# Clock_Distribution_PLL.net
KiCad netlist of a schematic drawn in Altium Designer
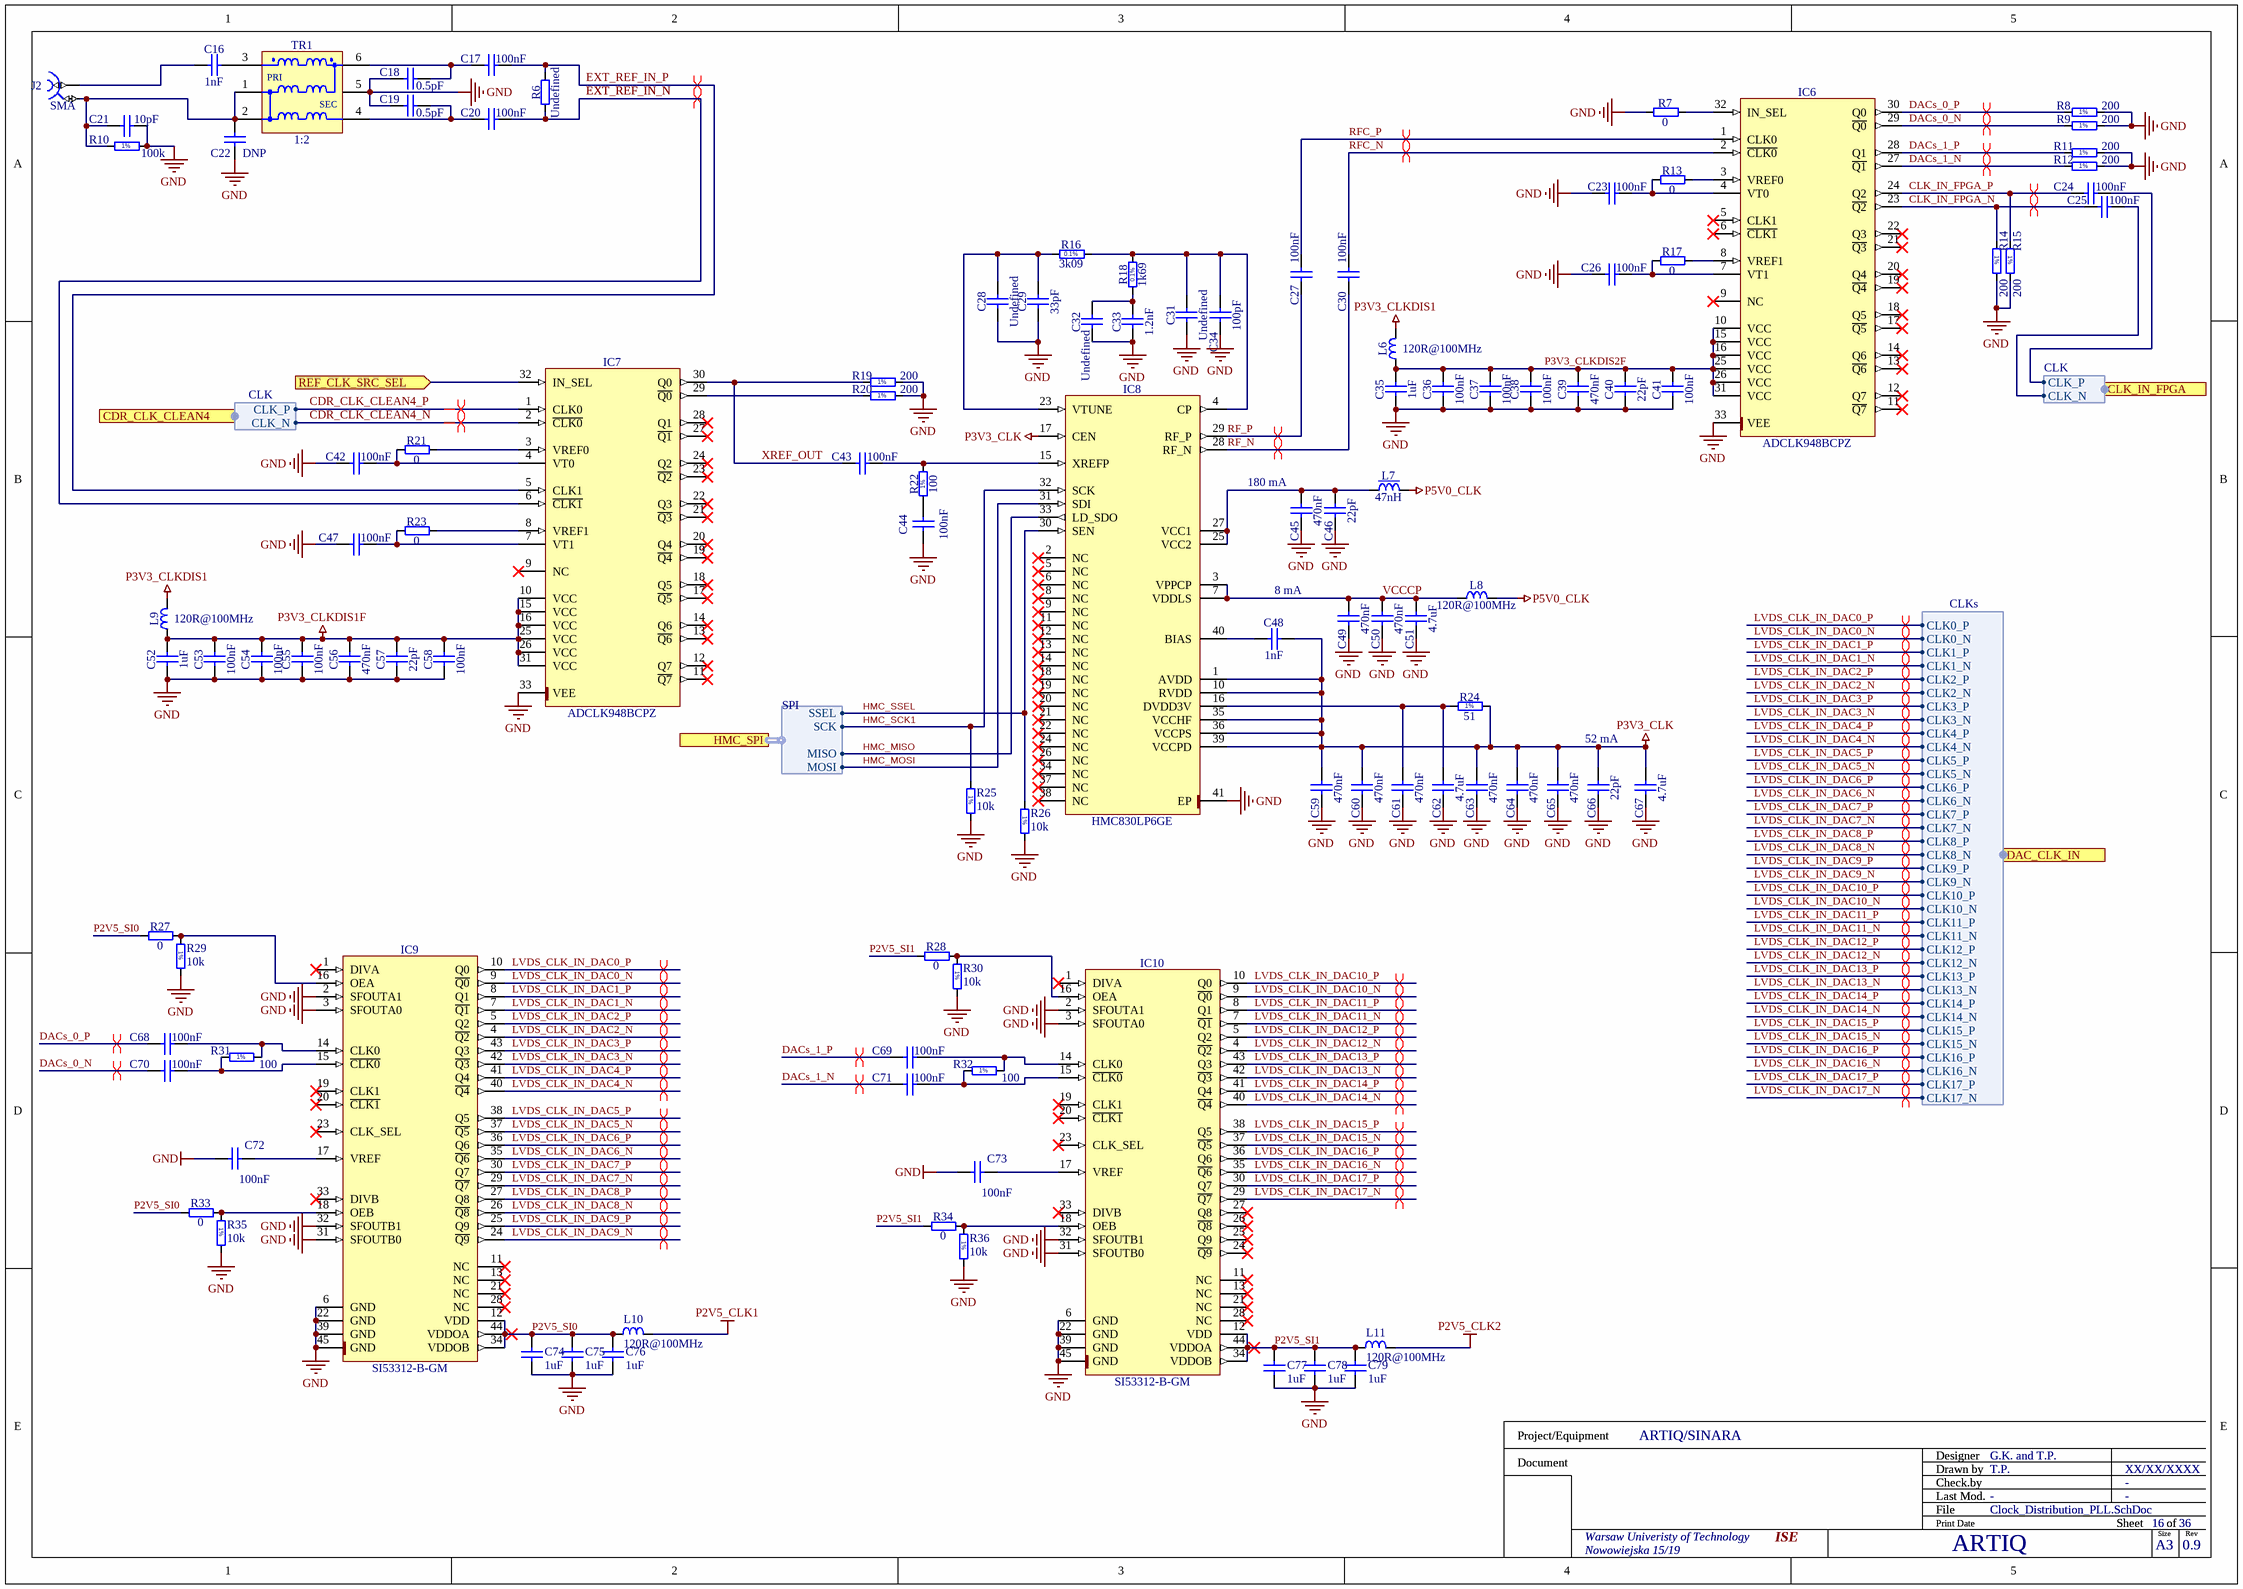
[diagram p0: Clock_Distribution_PLL.SchDoc]

(export (version "E")
  (design (tool "Eeschema 10.0.6"))
  (components
    (comp (ref "C16")
      (value "1nF")
      (footprint "CAPC1005X55N")
      (description "Non-polarised capacitor")
      (fields
        (field (name "PART NUMBER") "CC0402_1NF_50V_10%_X7R")
        (field (name "VOLTAGE") "50V")
        (field (name "AUTHOR") "CERN DEM JLC")
      )
      (libsource (lib "Capacitors") (part "Capacitor - non polarized"))
    )
    (comp (ref "C17")
      (value "100nF")
      (footprint "CAPC0603X33N")
      (description "Non-polarised capacitor")
      (fields
        (field (name "PART NUMBER") "CC0201_100NF_6.3V_10%_X5R")
        (field (name "VOLTAGE") "6.3V")
        (field (name "AUTHOR") "CERN DEM JLC")
      )
      (libsource (lib "Capacitors") (part "Capacitor - non polarized"))
    )
    (comp (ref "C18")
      (value "0.5pF")
      (footprint "CAPC1005X50N")
      (description "Non-polarised capacitor")
      (fields
        (field (name "PART NUMBER") "CC0402_0.5PF_25V_0.05PF_AVX_04023J0R5ABSTR")
        (field (name "VOLTAGE") "25V")
        (field (name "AUTHOR") "CERN DEM JLC")
      )
      (libsource (lib "Capacitors") (part "Capacitor - non polarized"))
    )
    (comp (ref "C19")
      (value "0.5pF")
      (footprint "CAPC1005X50N")
      (description "Non-polarised capacitor")
      (fields
        (field (name "PART NUMBER") "CC0402_0.5PF_25V_0.05PF_AVX_04023J0R5ABSTR")
        (field (name "VOLTAGE") "25V")
        (field (name "AUTHOR") "CERN DEM JLC")
      )
      (libsource (lib "Capacitors") (part "Capacitor - non polarized"))
    )
    (comp (ref "C20")
      (value "100nF")
      (footprint "CAPC0603X33N")
      (description "Non-polarised capacitor")
      (fields
        (field (name "PART NUMBER") "CC0201_100NF_6.3V_10%_X5R")
        (field (name "VOLTAGE") "6.3V")
        (field (name "AUTHOR") "CERN DEM JLC")
      )
      (libsource (lib "Capacitors") (part "Capacitor - non polarized"))
    )
    (comp (ref "C21")
      (value "10pF")
      (footprint "CAPC1608X87N")
      (description "Non-polarised capacitor")
      (fields
        (field (name "PART NUMBER") "CC0603_10PF_50V_5%_NP0")
        (field (name "VOLTAGE") "50V")
        (field (name "AUTHOR") "CERN DEM JLC")
      )
      (libsource (lib "Capacitors") (part "Capacitor - non polarized"))
    )
    (comp (ref "C22")
      (value "DNP")
      (footprint "CAPC0603X33N")
      (description "Non-polarised capacitor")
      (fields
        (field (name "PART NUMBER") "CC0201_100NF_6.3V_10%_X5R")
        (field (name "VOLTAGE") "6.3V")
        (field (name "AUTHOR") "CERN DEM JLC")
      )
      (libsource (lib "Capacitors") (part "Capacitor - non polarized"))
    )
    (comp (ref "C23")
      (value "100nF")
      (footprint "CAPC0603X33N")
      (description "Non-polarised capacitor")
      (fields
        (field (name "PART NUMBER") "CC0201_100NF_6.3V_10%_X5R")
        (field (name "VOLTAGE") "6.3V")
        (field (name "AUTHOR") "CERN DEM JLC")
      )
      (libsource (lib "Capacitors") (part "Capacitor - non polarized"))
    )
    (comp (ref "C24")
      (value "100nF")
      (footprint "CAPC0603X33N")
      (description "Non-polarised capacitor")
      (fields
        (field (name "PART NUMBER") "CC0201_100NF_6.3V_10%_X5R")
        (field (name "VOLTAGE") "6.3V")
        (field (name "AUTHOR") "CERN DEM JLC")
      )
      (libsource (lib "Capacitors") (part "Capacitor - non polarized"))
    )
    (comp (ref "C25")
      (value "100nF")
      (footprint "CAPC0603X33N")
      (description "Non-polarised capacitor")
      (fields
        (field (name "PART NUMBER") "CC0201_100NF_6.3V_10%_X5R")
        (field (name "VOLTAGE") "6.3V")
        (field (name "AUTHOR") "CERN DEM JLC")
      )
      (libsource (lib "Capacitors") (part "Capacitor - non polarized"))
    )
    (comp (ref "C26")
      (value "100nF")
      (footprint "CAPC0603X33N")
      (description "Non-polarised capacitor")
      (fields
        (field (name "PART NUMBER") "CC0201_100NF_6.3V_10%_X5R")
        (field (name "VOLTAGE") "6.3V")
        (field (name "AUTHOR") "CERN DEM JLC")
      )
      (libsource (lib "Capacitors") (part "Capacitor - non polarized"))
    )
    (comp (ref "C27")
      (value "100nF")
      (footprint "CAPC0603X33N")
      (description "Non-polarised capacitor")
      (fields
        (field (name "PART NUMBER") "CC0201_100NF_6.3V_10%_X5R")
        (field (name "VOLTAGE") "6.3V")
        (field (name "AUTHOR") "CERN DEM JLC")
      )
      (libsource (lib "Capacitors") (part "Capacitor - non polarized"))
    )
    (comp (ref "C28")
      (value "Undefined")
      (footprint "CAPC2012X135N")
      (description "Non-polarised capacitor")
      (fields
        (field (name "PART NUMBER") "Capacitor - non polarized CAPC2012X135N")
        (field (name "MANUFACTURER PART NUMBER") "CC0805_NO-VALUE")
        (field (name "AUTHOR") "CERN DEM JLC")
      )
      (libsource (lib "Capacitors") (part "Capacitor - non polarized"))
    )
    (comp (ref "C29")
      (value "33pF")
      (footprint "CAPC1608X87N")
      (description "Non-polarised capacitor")
      (fields
        (field (name "PART NUMBER") "CC0603_33PF_50V_5%_NP0")
        (field (name "VOLTAGE") "50V")
        (field (name "AUTHOR") "CERN DEM JLC")
      )
      (libsource (lib "Capacitors") (part "Capacitor - non polarized"))
    )
    (comp (ref "C30")
      (value "100nF")
      (footprint "CAPC0603X33N")
      (description "Non-polarised capacitor")
      (fields
        (field (name "PART NUMBER") "CC0201_100NF_6.3V_10%_X5R")
        (field (name "VOLTAGE") "6.3V")
        (field (name "AUTHOR") "CERN DEM JLC")
      )
      (libsource (lib "Capacitors") (part "Capacitor - non polarized"))
    )
    (comp (ref "C31")
      (value "Undefined")
      (footprint "CAPC2012X135N")
      (description "Non-polarised capacitor")
      (fields
        (field (name "PART NUMBER") "Capacitor - non polarized CAPC2012X135N")
        (field (name "MANUFACTURER PART NUMBER") "CC0805_NO-VALUE")
        (field (name "AUTHOR") "CERN DEM JLC")
      )
      (libsource (lib "Capacitors") (part "Capacitor - non polarized"))
    )
    (comp (ref "C32")
      (value "Undefined")
      (footprint "CAPC2012X135N")
      (description "Non-polarised capacitor")
      (fields
        (field (name "PART NUMBER") "Capacitor - non polarized CAPC2012X135N")
        (field (name "MANUFACTURER PART NUMBER") "CC0805_NO-VALUE")
        (field (name "AUTHOR") "CERN DEM JLC")
      )
      (libsource (lib "Capacitors") (part "Capacitor - non polarized"))
    )
    (comp (ref "C33")
      (value "1.2nF")
      (footprint "CAPC3216X140N")
      (description "Non-polarised capacitor")
      (fields
        (field (name "PART NUMBER") "CC1206_1.2NF_50V_5%_NP0")
        (field (name "VOLTAGE") "50V")
        (field (name "AUTHOR") "CERN DEM JLC")
      )
      (libsource (lib "Capacitors") (part "Capacitor - non polarized"))
    )
    (comp (ref "C34")
      (value "100pF")
      (footprint "CAPC1608X87N")
      (description "Non-polarised capacitor")
      (fields
        (field (name "PART NUMBER") "CC0603_100PF_50V_5%_NP0")
        (field (name "VOLTAGE") "50V")
        (field (name "AUTHOR") "CERN DEM JLC")
      )
      (libsource (lib "Capacitors") (part "Capacitor - non polarized"))
    )
    (comp (ref "C35")
      (value "1uF")
      (footprint "CAPC1005X55N")
      (description "Non-polarised capacitor")
      (fields
        (field (name "PART NUMBER") "CC0402_1UF_16V_10%_X5R")
        (field (name "VOLTAGE") "16V")
        (field (name "AUTHOR") "CERN DEM JLC")
      )
      (libsource (lib "Capacitors") (part "Capacitor - non polarized"))
    )
    (comp (ref "C36")
      (value "100nF")
      (footprint "CAPC0603X33N")
      (description "Non-polarised capacitor")
      (fields
        (field (name "PART NUMBER") "CC0201_100NF_6.3V_10%_X5R")
        (field (name "VOLTAGE") "6.3V")
        (field (name "AUTHOR") "CERN DEM JLC")
      )
      (libsource (lib "Capacitors") (part "Capacitor - non polarized"))
    )
    (comp (ref "C37")
      (value "100nF")
      (footprint "CAPC0603X33N")
      (description "Non-polarised capacitor")
      (fields
        (field (name "PART NUMBER") "CC0201_100NF_6.3V_10%_X5R")
        (field (name "VOLTAGE") "6.3V")
        (field (name "AUTHOR") "CERN DEM JLC")
      )
      (libsource (lib "Capacitors") (part "Capacitor - non polarized"))
    )
    (comp (ref "C38")
      (value "100nF")
      (footprint "CAPC0603X33N")
      (description "Non-polarised capacitor")
      (fields
        (field (name "PART NUMBER") "CC0201_100NF_6.3V_10%_X5R")
        (field (name "VOLTAGE") "6.3V")
        (field (name "AUTHOR") "CERN DEM JLC")
      )
      (libsource (lib "Capacitors") (part "Capacitor - non polarized"))
    )
    (comp (ref "C39")
      (value "470nF")
      (footprint "CAPC1005X55N")
      (description "Non-polarised capacitor")
      (fields
        (field (name "PART NUMBER") "CC0402_470NF_16V_10%_X5R")
        (field (name "VOLTAGE") "16V")
        (field (name "AUTHOR") "CERN DEM JLC")
      )
      (libsource (lib "Capacitors") (part "Capacitor - non polarized"))
    )
    (comp (ref "C40")
      (value "22pF")
      (footprint "CAPC1005X55N")
      (description "Non-polarised capacitor")
      (fields
        (field (name "PART NUMBER") "CC0402_22PF_50V_5%_C0G")
        (field (name "VOLTAGE") "50V")
        (field (name "AUTHOR") "CERN DEM JLC")
      )
      (libsource (lib "Capacitors") (part "Capacitor - non polarized"))
    )
    (comp (ref "C41")
      (value "100nF")
      (footprint "CAPC0603X33N")
      (description "Non-polarised capacitor")
      (fields
        (field (name "PART NUMBER") "CC0201_100NF_6.3V_10%_X5R")
        (field (name "VOLTAGE") "6.3V")
        (field (name "AUTHOR") "CERN DEM JLC")
      )
      (libsource (lib "Capacitors") (part "Capacitor - non polarized"))
    )
    (comp (ref "C42")
      (value "100nF")
      (footprint "CAPC0603X33N")
      (description "Non-polarised capacitor")
      (fields
        (field (name "PART NUMBER") "CC0201_100NF_6.3V_10%_X5R")
        (field (name "VOLTAGE") "6.3V")
        (field (name "AUTHOR") "CERN DEM JLC")
      )
      (libsource (lib "Capacitors") (part "Capacitor - non polarized"))
    )
    (comp (ref "C43")
      (value "100nF")
      (footprint "CAPC0603X33N")
      (description "Non-polarised capacitor")
      (fields
        (field (name "PART NUMBER") "CC0201_100NF_6.3V_10%_X5R")
        (field (name "VOLTAGE") "6.3V")
        (field (name "AUTHOR") "CERN DEM JLC")
      )
      (libsource (lib "Capacitors") (part "Capacitor - non polarized"))
    )
    (comp (ref "C44")
      (value "100nF")
      (footprint "CAPC0603X33N")
      (description "Non-polarised capacitor")
      (fields
        (field (name "PART NUMBER") "CC0201_100NF_6.3V_10%_X5R")
        (field (name "VOLTAGE") "6.3V")
        (field (name "AUTHOR") "CERN DEM JLC")
      )
      (libsource (lib "Capacitors") (part "Capacitor - non polarized"))
    )
    (comp (ref "C45")
      (value "470nF")
      (footprint "CAPC1005X55N")
      (description "Non-polarised capacitor")
      (fields
        (field (name "PART NUMBER") "CC0402_470NF_16V_10%_X5R")
        (field (name "VOLTAGE") "16V")
        (field (name "AUTHOR") "CERN DEM JLC")
      )
      (libsource (lib "Capacitors") (part "Capacitor - non polarized"))
    )
    (comp (ref "C46")
      (value "22pF")
      (footprint "CAPC1005X55N")
      (description "Non-polarised capacitor")
      (fields
        (field (name "PART NUMBER") "CC0402_22PF_50V_5%_C0G")
        (field (name "VOLTAGE") "50V")
        (field (name "AUTHOR") "CERN DEM JLC")
      )
      (libsource (lib "Capacitors") (part "Capacitor - non polarized"))
    )
    (comp (ref "C47")
      (value "100nF")
      (footprint "CAPC0603X33N")
      (description "Non-polarised capacitor")
      (fields
        (field (name "PART NUMBER") "CC0201_100NF_6.3V_10%_X5R")
        (field (name "VOLTAGE") "6.3V")
        (field (name "AUTHOR") "CERN DEM JLC")
      )
      (libsource (lib "Capacitors") (part "Capacitor - non polarized"))
    )
    (comp (ref "C48")
      (value "1nF")
      (footprint "CAPC1005X55N")
      (description "Non-polarised capacitor")
      (fields
        (field (name "PART NUMBER") "CC0402_1NF_50V_10%_X7R")
        (field (name "VOLTAGE") "50V")
        (field (name "AUTHOR") "CERN DEM JLC")
      )
      (libsource (lib "Capacitors") (part "Capacitor - non polarized"))
    )
    (comp (ref "C49")
      (value "470nF")
      (footprint "CAPC1005X55N")
      (description "Non-polarised capacitor")
      (fields
        (field (name "PART NUMBER") "CC0402_470NF_16V_10%_X5R")
        (field (name "VOLTAGE") "16V")
        (field (name "AUTHOR") "CERN DEM JLC")
      )
      (libsource (lib "Capacitors") (part "Capacitor - non polarized"))
    )
    (comp (ref "C50")
      (value "470nF")
      (footprint "CAPC1005X55N")
      (description "Non-polarised capacitor")
      (fields
        (field (name "PART NUMBER") "CC0402_470NF_16V_10%_X5R")
        (field (name "VOLTAGE") "16V")
        (field (name "AUTHOR") "CERN DEM JLC")
      )
      (libsource (lib "Capacitors") (part "Capacitor - non polarized"))
    )
    (comp (ref "C51")
      (value "4.7uF")
      (footprint "CAPC1608X90N")
      (description "Non-polarised capacitor")
      (fields
        (field (name "PART NUMBER") "CC0603_4.7UF_25V_10%_X5R")
        (field (name "VOLTAGE") "25V")
        (field (name "AUTHOR") "CERN DEM JLC")
      )
      (libsource (lib "Capacitors") (part "Capacitor - non polarized"))
    )
    (comp (ref "C52")
      (value "1uF")
      (footprint "CAPC1005X55N")
      (description "Non-polarised capacitor")
      (fields
        (field (name "PART NUMBER") "CC0402_1UF_16V_10%_X5R")
        (field (name "VOLTAGE") "16V")
        (field (name "AUTHOR") "CERN DEM JLC")
      )
      (libsource (lib "Capacitors") (part "Capacitor - non polarized"))
    )
    (comp (ref "C53")
      (value "100nF")
      (footprint "CAPC0603X33N")
      (description "Non-polarised capacitor")
      (fields
        (field (name "PART NUMBER") "CC0201_100NF_6.3V_10%_X5R")
        (field (name "VOLTAGE") "6.3V")
        (field (name "AUTHOR") "CERN DEM JLC")
      )
      (libsource (lib "Capacitors") (part "Capacitor - non polarized"))
    )
    (comp (ref "C54")
      (value "100nF")
      (footprint "CAPC0603X33N")
      (description "Non-polarised capacitor")
      (fields
        (field (name "PART NUMBER") "CC0201_100NF_6.3V_10%_X5R")
        (field (name "VOLTAGE") "6.3V")
        (field (name "AUTHOR") "CERN DEM JLC")
      )
      (libsource (lib "Capacitors") (part "Capacitor - non polarized"))
    )
    (comp (ref "C55")
      (value "100nF")
      (footprint "CAPC0603X33N")
      (description "Non-polarised capacitor")
      (fields
        (field (name "PART NUMBER") "CC0201_100NF_6.3V_10%_X5R")
        (field (name "VOLTAGE") "6.3V")
        (field (name "AUTHOR") "CERN DEM JLC")
      )
      (libsource (lib "Capacitors") (part "Capacitor - non polarized"))
    )
    (comp (ref "C56")
      (value "470nF")
      (footprint "CAPC1005X55N")
      (description "Non-polarised capacitor")
      (fields
        (field (name "PART NUMBER") "CC0402_470NF_16V_10%_X5R")
        (field (name "VOLTAGE") "16V")
        (field (name "AUTHOR") "CERN DEM JLC")
      )
      (libsource (lib "Capacitors") (part "Capacitor - non polarized"))
    )
    (comp (ref "C57")
      (value "22pF")
      (footprint "CAPC1005X55N")
      (description "Non-polarised capacitor")
      (fields
        (field (name "PART NUMBER") "CC0402_22PF_50V_5%_C0G")
        (field (name "VOLTAGE") "50V")
        (field (name "AUTHOR") "CERN DEM JLC")
      )
      (libsource (lib "Capacitors") (part "Capacitor - non polarized"))
    )
    (comp (ref "C58")
      (value "100nF")
      (footprint "CAPC0603X33N")
      (description "Non-polarised capacitor")
      (fields
        (field (name "PART NUMBER") "CC0201_100NF_6.3V_10%_X5R")
        (field (name "VOLTAGE") "6.3V")
        (field (name "AUTHOR") "CERN DEM JLC")
      )
      (libsource (lib "Capacitors") (part "Capacitor - non polarized"))
    )
    (comp (ref "C59")
      (value "470nF")
      (footprint "CAPC1005X55N")
      (description "Non-polarised capacitor")
      (fields
        (field (name "PART NUMBER") "CC0402_470NF_16V_10%_X5R")
        (field (name "VOLTAGE") "16V")
        (field (name "AUTHOR") "CERN DEM JLC")
      )
      (libsource (lib "Capacitors") (part "Capacitor - non polarized"))
    )
    (comp (ref "C60")
      (value "470nF")
      (footprint "CAPC1005X55N")
      (description "Non-polarised capacitor")
      (fields
        (field (name "PART NUMBER") "CC0402_470NF_16V_10%_X5R")
        (field (name "VOLTAGE") "16V")
        (field (name "AUTHOR") "CERN DEM JLC")
      )
      (libsource (lib "Capacitors") (part "Capacitor - non polarized"))
    )
    (comp (ref "C61")
      (value "470nF")
      (footprint "CAPC1005X55N")
      (description "Non-polarised capacitor")
      (fields
        (field (name "PART NUMBER") "CC0402_470NF_16V_10%_X5R")
        (field (name "VOLTAGE") "16V")
        (field (name "AUTHOR") "CERN DEM JLC")
      )
      (libsource (lib "Capacitors") (part "Capacitor - non polarized"))
    )
    (comp (ref "C62")
      (value "4.7uF")
      (footprint "CAPC1608X90N")
      (description "Non-polarised capacitor")
      (fields
        (field (name "PART NUMBER") "CC0603_4.7UF_25V_10%_X5R")
        (field (name "VOLTAGE") "25V")
        (field (name "AUTHOR") "CERN DEM JLC")
      )
      (libsource (lib "Capacitors") (part "Capacitor - non polarized"))
    )
    (comp (ref "C63")
      (value "470nF")
      (footprint "CAPC1005X55N")
      (description "Non-polarised capacitor")
      (fields
        (field (name "PART NUMBER") "CC0402_470NF_16V_10%_X5R")
        (field (name "VOLTAGE") "16V")
        (field (name "AUTHOR") "CERN DEM JLC")
      )
      (libsource (lib "Capacitors") (part "Capacitor - non polarized"))
    )
    (comp (ref "C64")
      (value "470nF")
      (footprint "CAPC1005X55N")
      (description "Non-polarised capacitor")
      (fields
        (field (name "PART NUMBER") "CC0402_470NF_16V_10%_X5R")
        (field (name "VOLTAGE") "16V")
        (field (name "AUTHOR") "CERN DEM JLC")
      )
      (libsource (lib "Capacitors") (part "Capacitor - non polarized"))
    )
    (comp (ref "C65")
      (value "470nF")
      (footprint "CAPC1005X55N")
      (description "Non-polarised capacitor")
      (fields
        (field (name "PART NUMBER") "CC0402_470NF_16V_10%_X5R")
        (field (name "VOLTAGE") "16V")
        (field (name "AUTHOR") "CERN DEM JLC")
      )
      (libsource (lib "Capacitors") (part "Capacitor - non polarized"))
    )
    (comp (ref "C66")
      (value "22pF")
      (footprint "CAPC1005X55N")
      (description "Non-polarised capacitor")
      (fields
        (field (name "PART NUMBER") "CC0402_22PF_50V_5%_C0G")
        (field (name "VOLTAGE") "50V")
        (field (name "AUTHOR") "CERN DEM JLC")
      )
      (libsource (lib "Capacitors") (part "Capacitor - non polarized"))
    )
    (comp (ref "C67")
      (value "4.7uF")
      (footprint "CAPC1608X90N")
      (description "Non-polarised capacitor")
      (fields
        (field (name "PART NUMBER") "CC0603_4.7UF_25V_10%_X5R")
        (field (name "VOLTAGE") "25V")
        (field (name "AUTHOR") "CERN DEM JLC")
      )
      (libsource (lib "Capacitors") (part "Capacitor - non polarized"))
    )
    (comp (ref "C68")
      (value "100nF")
      (footprint "CAPC0603X33N")
      (description "Non-polarised capacitor")
      (fields
        (field (name "PART NUMBER") "CC0201_100NF_6.3V_10%_X5R")
        (field (name "VOLTAGE") "6.3V")
        (field (name "AUTHOR") "CERN DEM JLC")
      )
      (libsource (lib "Capacitors") (part "Capacitor - non polarized"))
    )
    (comp (ref "C69")
      (value "100nF")
      (footprint "CAPC0603X33N")
      (description "Non-polarised capacitor")
      (fields
        (field (name "PART NUMBER") "CC0201_100NF_6.3V_10%_X5R")
        (field (name "VOLTAGE") "6.3V")
        (field (name "AUTHOR") "CERN DEM JLC")
      )
      (libsource (lib "Capacitors") (part "Capacitor - non polarized"))
    )
    (comp (ref "C70")
      (value "100nF")
      (footprint "CAPC0603X33N")
      (description "Non-polarised capacitor")
      (fields
        (field (name "PART NUMBER") "CC0201_100NF_6.3V_10%_X5R")
        (field (name "VOLTAGE") "6.3V")
        (field (name "AUTHOR") "CERN DEM JLC")
      )
      (libsource (lib "Capacitors") (part "Capacitor - non polarized"))
    )
    (comp (ref "C71")
      (value "100nF")
      (footprint "CAPC0603X33N")
      (description "Non-polarised capacitor")
      (fields
        (field (name "PART NUMBER") "CC0201_100NF_6.3V_10%_X5R")
        (field (name "VOLTAGE") "6.3V")
        (field (name "AUTHOR") "CERN DEM JLC")
      )
      (libsource (lib "Capacitors") (part "Capacitor - non polarized"))
    )
    (comp (ref "C72")
      (value "100nF")
      (footprint "CAPC1005X55N")
      (description "Non-polarised capacitor")
      (fields
        (field (name "PART NUMBER") "CC0402_100NF_16V_10%_X5R")
        (field (name "VOLTAGE") "16V")
        (field (name "AUTHOR") "CERN DEM JLC")
      )
      (libsource (lib "Capacitors") (part "Capacitor - non polarized"))
    )
    (comp (ref "C73")
      (value "100nF")
      (footprint "CAPC1005X55N")
      (description "Non-polarised capacitor")
      (fields
        (field (name "PART NUMBER") "CC0402_100NF_16V_10%_X5R")
        (field (name "VOLTAGE") "16V")
        (field (name "AUTHOR") "CERN DEM JLC")
      )
      (libsource (lib "Capacitors") (part "Capacitor - non polarized"))
    )
    (comp (ref "C74")
      (value "1uF")
      (footprint "CAPC1005X55N")
      (description "Non-polarised capacitor")
      (fields
        (field (name "PART NUMBER") "CC0402_1UF_16V_10%_X5R")
        (field (name "VOLTAGE") "16V")
        (field (name "AUTHOR") "CERN DEM JLC")
      )
      (libsource (lib "Capacitors") (part "Capacitor - non polarized"))
    )
    (comp (ref "C75")
      (value "1uF")
      (footprint "CAPC1005X55N")
      (description "Non-polarised capacitor")
      (fields
        (field (name "PART NUMBER") "CC0402_1UF_16V_10%_X5R")
        (field (name "VOLTAGE") "16V")
        (field (name "AUTHOR") "CERN DEM JLC")
      )
      (libsource (lib "Capacitors") (part "Capacitor - non polarized"))
    )
    (comp (ref "C76")
      (value "1uF")
      (footprint "CAPC1005X55N")
      (description "Non-polarised capacitor")
      (fields
        (field (name "PART NUMBER") "CC0402_1UF_16V_10%_X5R")
        (field (name "VOLTAGE") "16V")
        (field (name "AUTHOR") "CERN DEM JLC")
      )
      (libsource (lib "Capacitors") (part "Capacitor - non polarized"))
    )
    (comp (ref "C77")
      (value "1uF")
      (footprint "CAPC1005X55N")
      (description "Non-polarised capacitor")
      (fields
        (field (name "PART NUMBER") "CC0402_1UF_16V_10%_X5R")
        (field (name "VOLTAGE") "16V")
        (field (name "AUTHOR") "CERN DEM JLC")
      )
      (libsource (lib "Capacitors") (part "Capacitor - non polarized"))
    )
    (comp (ref "C78")
      (value "1uF")
      (footprint "CAPC1005X55N")
      (description "Non-polarised capacitor")
      (fields
        (field (name "PART NUMBER") "CC0402_1UF_16V_10%_X5R")
        (field (name "VOLTAGE") "16V")
        (field (name "AUTHOR") "CERN DEM JLC")
      )
      (libsource (lib "Capacitors") (part "Capacitor - non polarized"))
    )
    (comp (ref "C79")
      (value "1uF")
      (footprint "CAPC1005X55N")
      (description "Non-polarised capacitor")
      (fields
        (field (name "PART NUMBER") "CC0402_1UF_16V_10%_X5R")
        (field (name "VOLTAGE") "16V")
        (field (name "AUTHOR") "CERN DEM JLC")
      )
      (libsource (lib "Capacitors") (part "Capacitor - non polarized"))
    )
    (comp (ref "IC6")
      (value "ADCLK948BCPZ")
      (footprint "QFN50P500X500X80-33N-S285")
      (description "Two Selectable Inputs, 8 LVPECL Outputs, SiGe Clock Fanout Buffer")
      (fields (field (name "MANUFACTURER") "ANALOG DEVICES") (field (name "AUTHOR") "CERN DEM MR"))
      (libsource (lib "ICs And Semiconductors") (part "ADCLK948"))
    )
    (comp (ref "IC7")
      (value "ADCLK948BCPZ")
      (footprint "QFN50P500X500X80-33N-S285")
      (description "Two Selectable Inputs, 8 LVPECL Outputs, SiGe Clock Fanout Buffer")
      (fields (field (name "MANUFACTURER") "ANALOG DEVICES") (field (name "AUTHOR") "CERN DEM MR"))
      (libsource (lib "ICs And Semiconductors") (part "ADCLK948"))
    )
    (comp (ref "IC8")
      (value "HMC830LP6GE")
      (footprint "QFN50P600X600X90-41N-S475")
      (description "Fractional-N PLL With Integrated VCO, 25 to 3000MHz")
      (fields (field (name "MANUFACTURER") "HITTITE MICROWAVE CORP") (field (name "AUTHOR") "CERN DEM JMW"))
      (libsource (lib "ICs And Semiconductors") (part "HMC830LP6GE"))
    )
    (comp (ref "IC9")
      (value "SI53312-B-GM")
      (footprint "QFN50P700X700X90-45N-S295")
      (description "2 Input/10 Output, Low Jitter Universal Buffer/Level Translator With 2:1 Input Mux (<1.25 GHZ)")
      (fields (field (name "MANUFACTURER") "SILICON LABS") (field (name "AUTHOR") "CERN DEM MR"))
      (libsource (lib "ICs And Semiconductors") (part "SI53312"))
    )
    (comp (ref "IC10")
      (value "SI53312-B-GM")
      (footprint "QFN50P700X700X90-45N-S295")
      (description "2 Input/10 Output, Low Jitter Universal Buffer/Level Translator With 2:1 Input Mux (<1.25 GHZ)")
      (fields (field (name "MANUFACTURER") "SILICON LABS") (field (name "AUTHOR") "CERN DEM MR"))
      (libsource (lib "ICs And Semiconductors") (part "SI53312"))
    )
    (comp (ref "J2")
      (value "SMA")
      (footprint "CINCH_142-0761-801")
      (fields
        (field (name "PART NUMBER") "CINCH_142-0761-801")
        (field (name "MANUFACTURER") "CINCH CONNECTIVITY")
        (field (name "MANUFACTURER PART NUMBER") "142-0761-801")
        (field (name "AUTHOR") "CERN DEM JLC")
      )
      (libsource (lib "Connectors") (part "Coax_1Female_1Shield"))
    )
    (comp (ref "L6")
      (value "120R@100MHz")
      (footprint "INDC1608X95N")
      (description "Inductor")
      (fields
        (field (name "PART NUMBER") "IND0603_MURATA_BLM18PG121SN1D")
        (field (name "POWER") "2A")
        (field (name "AUTHOR") "CERN DEM BC")
      )
      (libsource (lib "") (part "Inductor_1"))
    )
    (comp (ref "L7")
      (value "47nH")
      (footprint "INDC2014X145N")
      (description "Inductor With Core")
      (fields
        (field (name "PART NUMBER") "IND0805_47NH_5%_EPCOS_B82498B")
        (field (name "POWER") "500mA")
        (field (name "AUTHOR") "CERN DEM JLC")
      )
      (libsource (lib "Inductors & Transformers") (part "Inductor With Magnetic core"))
    )
    (comp (ref "L8")
      (value "120R@100MHz")
      (footprint "INDC1608X95N")
      (description "Inductor")
      (fields
        (field (name "PART NUMBER") "IND0603_MURATA_BLM18PG121SN1D")
        (field (name "POWER") "2A")
        (field (name "AUTHOR") "CERN DEM BC")
      )
      (libsource (lib "Inductors & Transformers") (part "Inductor"))
    )
    (comp (ref "L9")
      (value "120R@100MHz")
      (footprint "INDC1608X95N")
      (description "Inductor")
      (fields
        (field (name "PART NUMBER") "IND0603_MURATA_BLM18PG121SN1D")
        (field (name "POWER") "2A")
        (field (name "AUTHOR") "CERN DEM BC")
      )
      (libsource (lib "") (part "Inductor_1"))
    )
    (comp (ref "L10")
      (value "120R@100MHz")
      (footprint "INDC1608X95N")
      (description "Inductor")
      (fields
        (field (name "PART NUMBER") "IND0603_MURATA_BLM18PG121SN1D")
        (field (name "POWER") "2A")
        (field (name "AUTHOR") "CERN DEM BC")
      )
      (libsource (lib "Inductors & Transformers") (part "Inductor"))
    )
    (comp (ref "L11")
      (value "120R@100MHz")
      (footprint "INDC1608X95N")
      (description "Inductor")
      (fields
        (field (name "PART NUMBER") "IND0603_MURATA_BLM18PG121SN1D")
        (field (name "POWER") "2A")
        (field (name "AUTHOR") "CERN DEM BC")
      )
      (libsource (lib "Inductors & Transformers") (part "Inductor"))
    )
    (comp (ref "R6")
      (value "Undefined")
      (footprint "RESC1005X40N")
      (description "Resistor")
      (fields (field (name "PART NUMBER") "R0402_NO-VALUE") (field (name "AUTHOR") "CERN DEM JLC"))
      (libsource (lib "Resistors") (part "Resistor"))
    )
    (comp (ref "R7")
      (value "0")
      (footprint "RESC1005X40N")
      (description "Resistor")
      (fields
        (field (name "PART NUMBER") "R0402_0R_JUMPER")
        (field (name "MANUFACTURER") "GENERIC")
        (field (name "AUTHOR") "CERN DEM JLC")
      )
      (libsource (lib "Resistors") (part "Resistor"))
    )
    (comp (ref "R8")
      (value "200")
      (footprint "RESC1005X40N")
      (description "Resistor - 1%")
      (fields
        (field (name "PART NUMBER") "R0402_200R_1%_0.0625W_100PPM")
        (field (name "POWER") "0.0625W")
        (field (name "AUTHOR") "CERN DEM JLC")
      )
      (libsource (lib "Resistors") (part "Resistor - 1%"))
    )
    (comp (ref "R9")
      (value "200")
      (footprint "RESC1005X40N")
      (description "Resistor - 1%")
      (fields
        (field (name "PART NUMBER") "R0402_200R_1%_0.0625W_100PPM")
        (field (name "POWER") "0.0625W")
        (field (name "AUTHOR") "CERN DEM JLC")
      )
      (libsource (lib "Resistors") (part "Resistor - 1%"))
    )
    (comp (ref "R10")
      (value "100k")
      (footprint "RESC1608X55N")
      (description "Resistor - 1%")
      (fields
        (field (name "PART NUMBER") "R0603_100K_1%_0.1W_100PPM")
        (field (name "POWER") "0.1W")
        (field (name "AUTHOR") "CERN DEM JLC")
      )
      (libsource (lib "Resistors") (part "Resistor - 1%"))
    )
    (comp (ref "R11")
      (value "200")
      (footprint "RESC1005X40N")
      (description "Resistor - 1%")
      (fields
        (field (name "PART NUMBER") "R0402_200R_1%_0.0625W_100PPM")
        (field (name "POWER") "0.0625W")
        (field (name "AUTHOR") "CERN DEM JLC")
      )
      (libsource (lib "Resistors") (part "Resistor - 1%"))
    )
    (comp (ref "R12")
      (value "200")
      (footprint "RESC1005X40N")
      (description "Resistor - 1%")
      (fields
        (field (name "PART NUMBER") "R0402_200R_1%_0.0625W_100PPM")
        (field (name "POWER") "0.0625W")
        (field (name "AUTHOR") "CERN DEM JLC")
      )
      (libsource (lib "Resistors") (part "Resistor - 1%"))
    )
    (comp (ref "R13")
      (value "0")
      (footprint "RESC1005X40N")
      (description "Resistor")
      (fields
        (field (name "PART NUMBER") "R0402_0R_JUMPER")
        (field (name "MANUFACTURER") "GENERIC")
        (field (name "AUTHOR") "CERN DEM JLC")
      )
      (libsource (lib "Resistors") (part "Resistor"))
    )
    (comp (ref "R14")
      (value "200")
      (footprint "RESC1005X40N")
      (description "Resistor - 1%")
      (fields
        (field (name "PART NUMBER") "R0402_200R_1%_0.0625W_100PPM")
        (field (name "POWER") "0.0625W")
        (field (name "AUTHOR") "CERN DEM JLC")
      )
      (libsource (lib "Resistors") (part "Resistor - 1%"))
    )
    (comp (ref "R15")
      (value "200")
      (footprint "RESC1005X40N")
      (description "Resistor - 1%")
      (fields
        (field (name "PART NUMBER") "R0402_200R_1%_0.0625W_100PPM")
        (field (name "POWER") "0.0625W")
        (field (name "AUTHOR") "CERN DEM JLC")
      )
      (libsource (lib "Resistors") (part "Resistor - 1%"))
    )
    (comp (ref "R16")
      (value "3k09")
      (footprint "RESC1608X55N")
      (description "Resistor - 0.1%")
      (fields
        (field (name "PART NUMBER") "R0603_3K09_0.1%_0.063W_10PPM")
        (field (name "POWER") "0.063W")
        (field (name "AUTHOR") "CERN DEM JLC")
      )
      (libsource (lib "Resistors") (part "Resistor - 0.1%"))
    )
    (comp (ref "R17")
      (value "0")
      (footprint "RESC1005X40N")
      (description "Resistor")
      (fields
        (field (name "PART NUMBER") "R0402_0R_JUMPER")
        (field (name "MANUFACTURER") "GENERIC")
        (field (name "AUTHOR") "CERN DEM JLC")
      )
      (libsource (lib "Resistors") (part "Resistor"))
    )
    (comp (ref "R18")
      (value "1k69")
      (footprint "RESC1608X55N")
      (description "Resistor - 0.1%")
      (fields
        (field (name "PART NUMBER") "R0603_1K69_0.1%_0.063W_10PPM")
        (field (name "POWER") "0.063W")
        (field (name "AUTHOR") "CERN DEM JLC")
      )
      (libsource (lib "Resistors") (part "Resistor - 0.1%"))
    )
    (comp (ref "R19")
      (value "200")
      (footprint "RESC1005X40N")
      (description "Resistor - 1%")
      (fields
        (field (name "PART NUMBER") "R0402_200R_1%_0.0625W_100PPM")
        (field (name "POWER") "0.0625W")
        (field (name "AUTHOR") "CERN DEM JLC")
      )
      (libsource (lib "Resistors") (part "Resistor - 1%"))
    )
    (comp (ref "R20")
      (value "200")
      (footprint "RESC1005X40N")
      (description "Resistor - 1%")
      (fields
        (field (name "PART NUMBER") "R0402_200R_1%_0.0625W_100PPM")
        (field (name "POWER") "0.0625W")
        (field (name "AUTHOR") "CERN DEM JLC")
      )
      (libsource (lib "Resistors") (part "Resistor - 1%"))
    )
    (comp (ref "R21")
      (value "0")
      (footprint "RESC1005X40N")
      (description "Resistor")
      (fields
        (field (name "PART NUMBER") "R0402_0R_JUMPER")
        (field (name "MANUFACTURER") "GENERIC")
        (field (name "AUTHOR") "CERN DEM JLC")
      )
      (libsource (lib "Resistors") (part "Resistor"))
    )
    (comp (ref "R22")
      (value "100")
      (footprint "RESC1005X40N")
      (description "Resistor - 1%")
      (fields
        (field (name "PART NUMBER") "R0402_100R_1%_0.0625W_100PPM")
        (field (name "POWER") "0.0625W")
        (field (name "AUTHOR") "CERN DEM JLC")
      )
      (libsource (lib "Resistors") (part "Resistor - 1%"))
    )
    (comp (ref "R23")
      (value "0")
      (footprint "RESC1005X40N")
      (description "Resistor")
      (fields
        (field (name "PART NUMBER") "R0402_0R_JUMPER")
        (field (name "MANUFACTURER") "GENERIC")
        (field (name "AUTHOR") "CERN DEM JLC")
      )
      (libsource (lib "Resistors") (part "Resistor"))
    )
    (comp (ref "R24")
      (value "51")
      (footprint "RESC1005X40N")
      (description "Resistor - 1%")
      (fields
        (field (name "PART NUMBER") "R0402_51R_1%_0.0625W_100PPM")
        (field (name "POWER") "0.0625W")
        (field (name "AUTHOR") "CERN DEM JLC")
      )
      (libsource (lib "Resistors") (part "Resistor - 1%"))
    )
    (comp (ref "R25")
      (value "10k")
      (footprint "RESC1005X40N")
      (description "Resistor - 1%")
      (fields
        (field (name "PART NUMBER") "R0402_10K_1%_0.0625W_100PPM")
        (field (name "POWER") "0.0625W")
        (field (name "AUTHOR") "CERN DEM JLC")
      )
      (libsource (lib "Resistors") (part "Resistor - 1%"))
    )
    (comp (ref "R26")
      (value "10k")
      (footprint "RESC1005X40N")
      (description "Resistor - 1%")
      (fields
        (field (name "PART NUMBER") "R0402_10K_1%_0.0625W_100PPM")
        (field (name "POWER") "0.0625W")
        (field (name "AUTHOR") "CERN DEM JLC")
      )
      (libsource (lib "Resistors") (part "Resistor - 1%"))
    )
    (comp (ref "R27")
      (value "0")
      (footprint "RESC1608X55N")
      (description "Resistor")
      (fields
        (field (name "PART NUMBER") "R0603_0R_JUMPER")
        (field (name "MANUFACTURER") "GENERIC")
        (field (name "AUTHOR") "CERN DEM JLC")
      )
      (libsource (lib "Resistors") (part "Resistor"))
    )
    (comp (ref "R28")
      (value "0")
      (footprint "RESC1608X55N")
      (description "Resistor")
      (fields
        (field (name "PART NUMBER") "R0603_0R_JUMPER")
        (field (name "MANUFACTURER") "GENERIC")
        (field (name "AUTHOR") "CERN DEM JLC")
      )
      (libsource (lib "Resistors") (part "Resistor"))
    )
    (comp (ref "R29")
      (value "10k")
      (footprint "RESC1005X40N")
      (description "Resistor - 1%")
      (fields
        (field (name "PART NUMBER") "R0402_10K_1%_0.0625W_100PPM")
        (field (name "POWER") "0.0625W")
        (field (name "AUTHOR") "CERN DEM JLC")
      )
      (libsource (lib "Resistors") (part "Resistor - 1%"))
    )
    (comp (ref "R30")
      (value "10k")
      (footprint "RESC1005X40N")
      (description "Resistor - 1%")
      (fields
        (field (name "PART NUMBER") "R0402_10K_1%_0.0625W_100PPM")
        (field (name "POWER") "0.0625W")
        (field (name "AUTHOR") "CERN DEM JLC")
      )
      (libsource (lib "Resistors") (part "Resistor - 1%"))
    )
    (comp (ref "R31")
      (value "100")
      (footprint "RESC0603X28N")
      (description "Resistor - 1%")
      (fields
        (field (name "PART NUMBER") "R0201_100R_1%_0.05W_200PPM")
        (field (name "POWER") "0.05W")
        (field (name "AUTHOR") "CERN DEM JLC")
      )
      (libsource (lib "Resistors") (part "Resistor - 1%"))
    )
    (comp (ref "R32")
      (value "100")
      (footprint "RESC0603X28N")
      (description "Resistor - 1%")
      (fields
        (field (name "PART NUMBER") "R0201_100R_1%_0.05W_200PPM")
        (field (name "POWER") "0.05W")
        (field (name "AUTHOR") "CERN DEM JLC")
      )
      (libsource (lib "Resistors") (part "Resistor - 1%"))
    )
    (comp (ref "R33")
      (value "0")
      (footprint "RESC1608X55N")
      (description "Resistor")
      (fields
        (field (name "PART NUMBER") "R0603_0R_JUMPER")
        (field (name "MANUFACTURER") "GENERIC")
        (field (name "AUTHOR") "CERN DEM JLC")
      )
      (libsource (lib "Resistors") (part "Resistor"))
    )
    (comp (ref "R34")
      (value "0")
      (footprint "RESC1608X55N")
      (description "Resistor")
      (fields
        (field (name "PART NUMBER") "R0603_0R_JUMPER")
        (field (name "MANUFACTURER") "GENERIC")
        (field (name "AUTHOR") "CERN DEM JLC")
      )
      (libsource (lib "Resistors") (part "Resistor"))
    )
    (comp (ref "R35")
      (value "10k")
      (footprint "RESC1005X40N")
      (description "Resistor - 1%")
      (fields
        (field (name "PART NUMBER") "R0402_10K_1%_0.0625W_100PPM")
        (field (name "POWER") "0.0625W")
        (field (name "AUTHOR") "CERN DEM JLC")
      )
      (libsource (lib "Resistors") (part "Resistor - 1%"))
    )
    (comp (ref "R36")
      (value "10k")
      (footprint "RESC1005X40N")
      (description "Resistor - 1%")
      (fields
        (field (name "PART NUMBER") "R0402_10K_1%_0.0625W_100PPM")
        (field (name "POWER") "0.0625W")
        (field (name "AUTHOR") "CERN DEM JLC")
      )
      (libsource (lib "Resistors") (part "Resistor - 1%"))
    )
    (comp (ref "TR1")
      (value "1:2")
      (footprint "XFMR_MINI-CIRCUITS_DB1627")
      (description "50 OHMS 10 to 4000 MHz RF Transformer")
      (fields
        (field (name "PART NUMBER") "XFMR_MINI-CIRCUITS_TCM2-43X+")
        (field (name "POWER") "0.4W")
        (field (name "AUTHOR") "CERN DEM BC")
      )
      (libsource (lib "Inductors & Transformers") (part "XFMR_MINI-CIRCUITS_TCM2-43X"))
    )
  )
  (nets
    (net (code "4") (name "/CDR_CLK_CLEAN4_N") (class "Default")
      (node (ref "IC7") (pin "2") (pinfunction "~{CLK0}_2") (pintype "input"))
    )
    (net (code "5") (name "/CDR_CLK_CLEAN4_P") (class "Default")
      (node (ref "IC7") (pin "1") (pinfunction "CLK0_1") (pintype "input"))
    )
    (net (code "6") (name "/CLK_IN_FPGA_N") (class "Default")
      (node (ref "C25") (pin "1") (pinfunction "1_1") (pintype "passive"))
      (node (ref "IC6") (pin "23") (pinfunction "~{Q2}_23") (pintype "output"))
      (node (ref "R14") (pin "1") (pinfunction "1_1") (pintype "passive"))
    )
    (net (code "7") (name "/CLK_IN_FPGA_P") (class "Default")
      (node (ref "C24") (pin "1") (pinfunction "1_1") (pintype "passive"))
      (node (ref "IC6") (pin "24") (pinfunction "Q2_24") (pintype "output"))
      (node (ref "R15") (pin "1") (pinfunction "1_1") (pintype "passive"))
    )
    (net (code "8") (name "/DACs_0_N") (class "Default")
      (node (ref "C70") (pin "1") (pinfunction "1_1") (pintype "passive"))
      (node (ref "IC6") (pin "29") (pinfunction "~{Q0}_29") (pintype "output"))
      (node (ref "R9") (pin "1") (pinfunction "1_1") (pintype "passive"))
    )
    (net (code "9") (name "/DACs_0_P") (class "Default")
      (node (ref "C68") (pin "1") (pinfunction "1_1") (pintype "passive"))
      (node (ref "IC6") (pin "30") (pinfunction "Q0_30") (pintype "output"))
      (node (ref "R8") (pin "1") (pinfunction "1_1") (pintype "passive"))
    )
    (net (code "10") (name "/DACs_1_N") (class "Default")
      (node (ref "C71") (pin "1") (pinfunction "1_1") (pintype "passive"))
      (node (ref "IC6") (pin "27") (pinfunction "~{Q1}_27") (pintype "output"))
      (node (ref "R12") (pin "1") (pinfunction "1_1") (pintype "passive"))
    )
    (net (code "11") (name "/DACs_1_P") (class "Default")
      (node (ref "C69") (pin "1") (pinfunction "1_1") (pintype "passive"))
      (node (ref "IC6") (pin "28") (pinfunction "Q1_28") (pintype "output"))
      (node (ref "R11") (pin "1") (pinfunction "1_1") (pintype "passive"))
    )
    (net (code "12") (name "/EXT_REF_IN_N") (class "Default")
      (node (ref "C20") (pin "2") (pinfunction "2_2") (pintype "passive"))
      (node (ref "IC7") (pin "6") (pinfunction "~{CLK1}_6") (pintype "input"))
      (node (ref "R6") (pin "1") (pinfunction "1_1") (pintype "passive"))
    )
    (net (code "13") (name "/EXT_REF_IN_P") (class "Default")
      (node (ref "C17") (pin "2") (pinfunction "2_2") (pintype "passive"))
      (node (ref "IC7") (pin "5") (pinfunction "CLK1_5") (pintype "input"))
      (node (ref "R6") (pin "2") (pinfunction "2_2") (pintype "passive"))
    )
    (net (code "14") (name "/HMC_MISO") (class "Default")
      (node (ref "IC8") (pin "33") (pinfunction "LD_SDO_33") (pintype "output"))
    )
    (net (code "15") (name "/HMC_MOSI") (class "Default")
      (node (ref "IC8") (pin "31") (pinfunction "SDI_31") (pintype "input"))
    )
    (net (code "16") (name "/HMC_SCK1") (class "Default")
      (node (ref "IC8") (pin "32") (pinfunction "SCK_32") (pintype "input"))
      (node (ref "R25") (pin "1") (pinfunction "1_1") (pintype "passive"))
    )
    (net (code "17") (name "/HMC_SSEL") (class "Default")
      (node (ref "IC8") (pin "30") (pinfunction "SEN_30") (pintype "input"))
      (node (ref "R26") (pin "1") (pinfunction "1_1") (pintype "passive"))
    )
    (net (code "18") (name "/LVDS_CLK_IN_DAC0_N") (class "Default")
      (node (ref "IC9") (pin "9") (pinfunction "~{Q0}_9") (pintype "output"))
    )
    (net (code "19") (name "/LVDS_CLK_IN_DAC0_P") (class "Default")
      (node (ref "IC9") (pin "10") (pinfunction "Q0_10") (pintype "output"))
    )
    (net (code "20") (name "/LVDS_CLK_IN_DAC1_N") (class "Default")
      (node (ref "IC9") (pin "7") (pinfunction "~{Q1}_7") (pintype "output"))
    )
    (net (code "21") (name "/LVDS_CLK_IN_DAC1_P") (class "Default")
      (node (ref "IC9") (pin "8") (pinfunction "Q1_8") (pintype "output"))
    )
    (net (code "22") (name "/LVDS_CLK_IN_DAC2_N") (class "Default")
      (node (ref "IC9") (pin "4") (pinfunction "~{Q2}_4") (pintype "output"))
    )
    (net (code "23") (name "/LVDS_CLK_IN_DAC2_P") (class "Default")
      (node (ref "IC9") (pin "5") (pinfunction "Q2_5") (pintype "output"))
    )
    (net (code "24") (name "/LVDS_CLK_IN_DAC3_N") (class "Default")
      (node (ref "IC9") (pin "42") (pinfunction "~{Q3}_42") (pintype "output"))
    )
    (net (code "25") (name "/LVDS_CLK_IN_DAC3_P") (class "Default")
      (node (ref "IC9") (pin "43") (pinfunction "Q3_43") (pintype "output"))
    )
    (net (code "26") (name "/LVDS_CLK_IN_DAC4_N") (class "Default")
      (node (ref "IC9") (pin "40") (pinfunction "~{Q4}_40") (pintype "output"))
    )
    (net (code "27") (name "/LVDS_CLK_IN_DAC4_P") (class "Default")
      (node (ref "IC9") (pin "41") (pinfunction "Q4_41") (pintype "output"))
    )
    (net (code "28") (name "/LVDS_CLK_IN_DAC5_N") (class "Default")
      (node (ref "IC9") (pin "37") (pinfunction "~{Q5}_37") (pintype "output"))
    )
    (net (code "29") (name "/LVDS_CLK_IN_DAC5_P") (class "Default")
      (node (ref "IC9") (pin "38") (pinfunction "Q5_38") (pintype "output"))
    )
    (net (code "30") (name "/LVDS_CLK_IN_DAC6_N") (class "Default")
      (node (ref "IC9") (pin "35") (pinfunction "~{Q6}_35") (pintype "output"))
    )
    (net (code "31") (name "/LVDS_CLK_IN_DAC6_P") (class "Default")
      (node (ref "IC9") (pin "36") (pinfunction "Q6_36") (pintype "output"))
    )
    (net (code "32") (name "/LVDS_CLK_IN_DAC7_N") (class "Default")
      (node (ref "IC9") (pin "29") (pinfunction "~{Q7}_29") (pintype "output"))
    )
    (net (code "33") (name "/LVDS_CLK_IN_DAC7_P") (class "Default")
      (node (ref "IC9") (pin "30") (pinfunction "Q7_30") (pintype "output"))
    )
    (net (code "34") (name "/LVDS_CLK_IN_DAC8_N") (class "Default")
      (node (ref "IC9") (pin "26") (pinfunction "~{Q8}_26") (pintype "output"))
    )
    (net (code "35") (name "/LVDS_CLK_IN_DAC8_P") (class "Default")
      (node (ref "IC9") (pin "27") (pinfunction "Q8_27") (pintype "output"))
    )
    (net (code "36") (name "/LVDS_CLK_IN_DAC9_N") (class "Default")
      (node (ref "IC9") (pin "24") (pinfunction "~{Q9}_24") (pintype "output"))
    )
    (net (code "37") (name "/LVDS_CLK_IN_DAC9_P") (class "Default")
      (node (ref "IC9") (pin "25") (pinfunction "Q9_25") (pintype "output"))
    )
    (net (code "38") (name "/LVDS_CLK_IN_DAC10_N") (class "Default")
      (node (ref "IC10") (pin "9") (pinfunction "~{Q0}_9") (pintype "output"))
    )
    (net (code "39") (name "/LVDS_CLK_IN_DAC10_P") (class "Default")
      (node (ref "IC10") (pin "10") (pinfunction "Q0_10") (pintype "output"))
    )
    (net (code "40") (name "/LVDS_CLK_IN_DAC11_N") (class "Default")
      (node (ref "IC10") (pin "7") (pinfunction "~{Q1}_7") (pintype "output"))
    )
    (net (code "41") (name "/LVDS_CLK_IN_DAC11_P") (class "Default")
      (node (ref "IC10") (pin "8") (pinfunction "Q1_8") (pintype "output"))
    )
    (net (code "42") (name "/LVDS_CLK_IN_DAC12_N") (class "Default")
      (node (ref "IC10") (pin "4") (pinfunction "~{Q2}_4") (pintype "output"))
    )
    (net (code "43") (name "/LVDS_CLK_IN_DAC12_P") (class "Default")
      (node (ref "IC10") (pin "5") (pinfunction "Q2_5") (pintype "output"))
    )
    (net (code "44") (name "/LVDS_CLK_IN_DAC13_N") (class "Default")
      (node (ref "IC10") (pin "42") (pinfunction "~{Q3}_42") (pintype "output"))
    )
    (net (code "45") (name "/LVDS_CLK_IN_DAC13_P") (class "Default")
      (node (ref "IC10") (pin "43") (pinfunction "Q3_43") (pintype "output"))
    )
    (net (code "46") (name "/LVDS_CLK_IN_DAC14_N") (class "Default")
      (node (ref "IC10") (pin "40") (pinfunction "~{Q4}_40") (pintype "output"))
    )
    (net (code "47") (name "/LVDS_CLK_IN_DAC14_P") (class "Default")
      (node (ref "IC10") (pin "41") (pinfunction "Q4_41") (pintype "output"))
    )
    (net (code "48") (name "/LVDS_CLK_IN_DAC15_N") (class "Default")
      (node (ref "IC10") (pin "37") (pinfunction "~{Q5}_37") (pintype "output"))
    )
    (net (code "49") (name "/LVDS_CLK_IN_DAC15_P") (class "Default")
      (node (ref "IC10") (pin "38") (pinfunction "Q5_38") (pintype "output"))
    )
    (net (code "50") (name "/LVDS_CLK_IN_DAC16_N") (class "Default")
      (node (ref "IC10") (pin "35") (pinfunction "~{Q6}_35") (pintype "output"))
    )
    (net (code "51") (name "/LVDS_CLK_IN_DAC16_P") (class "Default")
      (node (ref "IC10") (pin "36") (pinfunction "Q6_36") (pintype "output"))
    )
    (net (code "52") (name "/LVDS_CLK_IN_DAC17_N") (class "Default")
      (node (ref "IC10") (pin "29") (pinfunction "~{Q7}_29") (pintype "output"))
    )
    (net (code "53") (name "/LVDS_CLK_IN_DAC17_P") (class "Default")
      (node (ref "IC10") (pin "30") (pinfunction "Q7_30") (pintype "output"))
    )
    (net (code "54") (name "/P2V5_SI0") (class "Default")
      (node (ref "C74") (pin "2") (pinfunction "2_2") (pintype "passive"))
      (node (ref "C75") (pin "2") (pinfunction "2_2") (pintype "passive"))
      (node (ref "C76") (pin "2") (pinfunction "2_2") (pintype "passive"))
      (node (ref "IC9") (pin "12") (pinfunction "VDD_12") (pintype "power_in"))
      (node (ref "IC9") (pin "34") (pinfunction "VDDOB_34") (pintype "output"))
      (node (ref "IC9") (pin "44") (pinfunction "VDDOA_44") (pintype "output"))
      (node (ref "L10") (pin "1") (pinfunction "1_1") (pintype "passive"))
      (node (ref "R27") (pin "1") (pinfunction "1_1") (pintype "passive"))
      (node (ref "R33") (pin "1") (pinfunction "1_1") (pintype "passive"))
    )
    (net (code "55") (name "/P2V5_SI1") (class "Default")
      (node (ref "C77") (pin "2") (pinfunction "2_2") (pintype "passive"))
      (node (ref "C78") (pin "2") (pinfunction "2_2") (pintype "passive"))
      (node (ref "C79") (pin "2") (pinfunction "2_2") (pintype "passive"))
      (node (ref "IC10") (pin "12") (pinfunction "VDD_12") (pintype "power_in"))
      (node (ref "IC10") (pin "34") (pinfunction "VDDOB_34") (pintype "output"))
      (node (ref "IC10") (pin "44") (pinfunction "VDDOA_44") (pintype "output"))
      (node (ref "L11") (pin "1") (pinfunction "1_1") (pintype "passive"))
      (node (ref "R28") (pin "1") (pinfunction "1_1") (pintype "passive"))
      (node (ref "R34") (pin "1") (pinfunction "1_1") (pintype "passive"))
    )
    (net (code "56") (name "/P3V3_CLKDIS2F") (class "Default")
      (node (ref "C35") (pin "2") (pinfunction "2_2") (pintype "passive"))
      (node (ref "C36") (pin "2") (pinfunction "2_2") (pintype "passive"))
      (node (ref "C37") (pin "2") (pinfunction "2_2") (pintype "passive"))
      (node (ref "C38") (pin "2") (pinfunction "2_2") (pintype "passive"))
      (node (ref "C39") (pin "2") (pinfunction "2_2") (pintype "passive"))
      (node (ref "C40") (pin "2") (pinfunction "2_2") (pintype "passive"))
      (node (ref "C41") (pin "2") (pinfunction "2_2") (pintype "passive"))
      (node (ref "IC6") (pin "10") (pinfunction "VCC_10") (pintype "power_in"))
      (node (ref "IC6") (pin "15") (pinfunction "VCC_15") (pintype "power_in"))
      (node (ref "IC6") (pin "16") (pinfunction "VCC_16") (pintype "power_in"))
      (node (ref "IC6") (pin "25") (pinfunction "VCC_25") (pintype "power_in"))
      (node (ref "IC6") (pin "26") (pinfunction "VCC_26") (pintype "power_in"))
      (node (ref "IC6") (pin "31") (pinfunction "VCC_31") (pintype "power_in"))
      (node (ref "L6") (pin "1") (pinfunction "1_1") (pintype "passive"))
    )
    (net (code "57") (name "/REF_CLK_SRC_SEL") (class "Default")
      (node (ref "IC7") (pin "32") (pinfunction "IN_SEL_32") (pintype "input"))
    )
    (net (code "58") (name "/RFC_N") (class "Default")
      (node (ref "C30") (pin "2") (pinfunction "2_2") (pintype "passive"))
      (node (ref "IC6") (pin "2") (pinfunction "~{CLK0}_2") (pintype "input"))
    )
    (net (code "59") (name "/RFC_P") (class "Default")
      (node (ref "C27") (pin "2") (pinfunction "2_2") (pintype "passive"))
      (node (ref "IC6") (pin "1") (pinfunction "CLK0_1") (pintype "input"))
    )
    (net (code "60") (name "/RF_N") (class "Default")
      (node (ref "C30") (pin "1") (pinfunction "1_1") (pintype "passive"))
      (node (ref "IC8") (pin "28") (pinfunction "RF_N_28") (pintype "output"))
    )
    (net (code "61") (name "/RF_P") (class "Default")
      (node (ref "C27") (pin "1") (pinfunction "1_1") (pintype "passive"))
      (node (ref "IC8") (pin "29") (pinfunction "RF_P_29") (pintype "output"))
    )
    (net (code "62") (name "/VCCCP") (class "Default")
      (node (ref "C49") (pin "2") (pinfunction "2_2") (pintype "passive"))
      (node (ref "C50") (pin "2") (pinfunction "2_2") (pintype "passive"))
      (node (ref "C51") (pin "2") (pinfunction "2_2") (pintype "passive"))
      (node (ref "IC8") (pin "3") (pinfunction "VPPCP_3") (pintype "power_in"))
      (node (ref "IC8") (pin "7") (pinfunction "VDDLS_7") (pintype "power_in"))
      (node (ref "L8") (pin "1") (pinfunction "1_1") (pintype "passive"))
    )
    (net (code "63") (name "/XREF_OUT") (class "Default")
      (node (ref "C43") (pin "1") (pinfunction "1_1") (pintype "passive"))
      (node (ref "IC7") (pin "30") (pinfunction "Q0_30") (pintype "output"))
      (node (ref "R19") (pin "1") (pinfunction "1_1") (pintype "passive"))
    )
    (net (code "67") (name "GND") (class "Default")
      (node (ref "C18") (pin "1") (pinfunction "1_1") (pintype "passive"))
      (node (ref "C19") (pin "1") (pinfunction "1_1") (pintype "passive"))
      (node (ref "C21") (pin "2") (pinfunction "2_2") (pintype "passive"))
      (node (ref "C22") (pin "1") (pinfunction "1_1") (pintype "passive"))
      (node (ref "C23") (pin "1") (pinfunction "1_1") (pintype "passive"))
      (node (ref "C26") (pin "1") (pinfunction "1_1") (pintype "passive"))
      (node (ref "C28") (pin "1") (pinfunction "1_1") (pintype "passive"))
      (node (ref "C29") (pin "1") (pinfunction "1_1") (pintype "passive"))
      (node (ref "C31") (pin "1") (pinfunction "1_1") (pintype "passive"))
      (node (ref "C32") (pin "1") (pinfunction "1_1") (pintype "passive"))
      (node (ref "C33") (pin "1") (pinfunction "1_1") (pintype "passive"))
      (node (ref "C34") (pin "1") (pinfunction "1_1") (pintype "passive"))
      (node (ref "C35") (pin "1") (pinfunction "1_1") (pintype "passive"))
      (node (ref "C36") (pin "1") (pinfunction "1_1") (pintype "passive"))
      (node (ref "C37") (pin "1") (pinfunction "1_1") (pintype "passive"))
      (node (ref "C38") (pin "1") (pinfunction "1_1") (pintype "passive"))
      (node (ref "C39") (pin "1") (pinfunction "1_1") (pintype "passive"))
      (node (ref "C40") (pin "1") (pinfunction "1_1") (pintype "passive"))
      (node (ref "C41") (pin "1") (pinfunction "1_1") (pintype "passive"))
      (node (ref "C42") (pin "1") (pinfunction "1_1") (pintype "passive"))
      (node (ref "C44") (pin "1") (pinfunction "1_1") (pintype "passive"))
      (node (ref "C45") (pin "1") (pinfunction "1_1") (pintype "passive"))
      (node (ref "C46") (pin "1") (pinfunction "1_1") (pintype "passive"))
      (node (ref "C47") (pin "1") (pinfunction "1_1") (pintype "passive"))
      (node (ref "C49") (pin "1") (pinfunction "1_1") (pintype "passive"))
      (node (ref "C50") (pin "1") (pinfunction "1_1") (pintype "passive"))
      (node (ref "C51") (pin "1") (pinfunction "1_1") (pintype "passive"))
      (node (ref "C52") (pin "1") (pinfunction "1_1") (pintype "passive"))
      (node (ref "C53") (pin "1") (pinfunction "1_1") (pintype "passive"))
      (node (ref "C54") (pin "1") (pinfunction "1_1") (pintype "passive"))
      (node (ref "C55") (pin "1") (pinfunction "1_1") (pintype "passive"))
      (node (ref "C56") (pin "1") (pinfunction "1_1") (pintype "passive"))
      (node (ref "C57") (pin "1") (pinfunction "1_1") (pintype "passive"))
      (node (ref "C58") (pin "1") (pinfunction "1_1") (pintype "passive"))
      (node (ref "C59") (pin "1") (pinfunction "1_1") (pintype "passive"))
      (node (ref "C60") (pin "1") (pinfunction "1_1") (pintype "passive"))
      (node (ref "C61") (pin "1") (pinfunction "1_1") (pintype "passive"))
      (node (ref "C62") (pin "1") (pinfunction "1_1") (pintype "passive"))
      (node (ref "C63") (pin "1") (pinfunction "1_1") (pintype "passive"))
      (node (ref "C64") (pin "1") (pinfunction "1_1") (pintype "passive"))
      (node (ref "C65") (pin "1") (pinfunction "1_1") (pintype "passive"))
      (node (ref "C66") (pin "1") (pinfunction "1_1") (pintype "passive"))
      (node (ref "C67") (pin "1") (pinfunction "1_1") (pintype "passive"))
      (node (ref "C72") (pin "1") (pinfunction "1_1") (pintype "passive"))
      (node (ref "C73") (pin "1") (pinfunction "1_1") (pintype "passive"))
      (node (ref "C74") (pin "1") (pinfunction "1_1") (pintype "passive"))
      (node (ref "C75") (pin "1") (pinfunction "1_1") (pintype "passive"))
      (node (ref "C76") (pin "1") (pinfunction "1_1") (pintype "passive"))
      (node (ref "C77") (pin "1") (pinfunction "1_1") (pintype "passive"))
      (node (ref "C78") (pin "1") (pinfunction "1_1") (pintype "passive"))
      (node (ref "C79") (pin "1") (pinfunction "1_1") (pintype "passive"))
      (node (ref "IC10") (pin "2") (pinfunction "SFOUTA1_2") (pintype "input"))
      (node (ref "IC10") (pin "22") (pinfunction "GND_22") (pintype "power_in"))
      (node (ref "IC10") (pin "3") (pinfunction "SFOUTA0_3") (pintype "input"))
      (node (ref "IC10") (pin "31") (pinfunction "SFOUTB0_31") (pintype "input"))
      (node (ref "IC10") (pin "32") (pinfunction "SFOUTB1_32") (pintype "input"))
      (node (ref "IC10") (pin "39") (pinfunction "GND_39") (pintype "power_in"))
      (node (ref "IC10") (pin "45") (pinfunction "GND_45") (pintype "power_in"))
      (node (ref "IC10") (pin "6") (pinfunction "GND_6") (pintype "power_in"))
      (node (ref "IC6") (pin "33") (pinfunction "VEE_33") (pintype "power_in"))
      (node (ref "IC7") (pin "33") (pinfunction "VEE_33") (pintype "power_in"))
      (node (ref "IC8") (pin "41") (pinfunction "EP_41") (pintype "power_in"))
      (node (ref "IC9") (pin "2") (pinfunction "SFOUTA1_2") (pintype "input"))
      (node (ref "IC9") (pin "22") (pinfunction "GND_22") (pintype "power_in"))
      (node (ref "IC9") (pin "3") (pinfunction "SFOUTA0_3") (pintype "input"))
      (node (ref "IC9") (pin "31") (pinfunction "SFOUTB0_31") (pintype "input"))
      (node (ref "IC9") (pin "32") (pinfunction "SFOUTB1_32") (pintype "input"))
      (node (ref "IC9") (pin "39") (pinfunction "GND_39") (pintype "power_in"))
      (node (ref "IC9") (pin "45") (pinfunction "GND_45") (pintype "power_in"))
      (node (ref "IC9") (pin "6") (pinfunction "GND_6") (pintype "power_in"))
      (node (ref "R10") (pin "2") (pinfunction "2_2") (pintype "passive"))
      (node (ref "R11") (pin "2") (pinfunction "2_2") (pintype "passive"))
      (node (ref "R12") (pin "2") (pinfunction "2_2") (pintype "passive"))
      (node (ref "R14") (pin "2") (pinfunction "2_2") (pintype "passive"))
      (node (ref "R15") (pin "2") (pinfunction "2_2") (pintype "passive"))
      (node (ref "R19") (pin "2") (pinfunction "2_2") (pintype "passive"))
      (node (ref "R20") (pin "2") (pinfunction "2_2") (pintype "passive"))
      (node (ref "R25") (pin "2") (pinfunction "2_2") (pintype "passive"))
      (node (ref "R26") (pin "2") (pinfunction "2_2") (pintype "passive"))
      (node (ref "R29") (pin "2") (pinfunction "2_2") (pintype "passive"))
      (node (ref "R30") (pin "2") (pinfunction "2_2") (pintype "passive"))
      (node (ref "R35") (pin "2") (pinfunction "2_2") (pintype "passive"))
      (node (ref "R36") (pin "2") (pinfunction "2_2") (pintype "passive"))
      (node (ref "R7") (pin "1") (pinfunction "1_1") (pintype "passive"))
      (node (ref "R8") (pin "2") (pinfunction "2_2") (pintype "passive"))
      (node (ref "R9") (pin "2") (pinfunction "2_2") (pintype "passive"))
      (node (ref "TR1") (pin "5") (pinfunction "NC_5") (pintype "passive"))
    )
    (net (code "68") (name "Net-(C16-Pad1)") (class "Default")
      (node (ref "C16") (pin "1") (pinfunction "1_1") (pintype "passive"))
      (node (ref "J2") (pin "1") (pinfunction "1_1") (pintype "bidirectional"))
    )
    (net (code "69") (name "Net-(C16-Pad2)") (class "Default")
      (node (ref "C16") (pin "2") (pinfunction "2_2") (pintype "passive"))
      (node (ref "TR1") (pin "3") (pinfunction "P1_3") (pintype "passive"))
    )
    (net (code "70") (name "Net-(C17-Pad1)") (class "Default")
      (node (ref "C17") (pin "1") (pinfunction "1_1") (pintype "passive"))
      (node (ref "C18") (pin "2") (pinfunction "2_2") (pintype "passive"))
      (node (ref "TR1") (pin "6") (pinfunction "S1_6") (pintype "passive"))
    )
    (net (code "71") (name "Net-(C19-Pad2)") (class "Default")
      (node (ref "C19") (pin "2") (pinfunction "2_2") (pintype "passive"))
      (node (ref "C20") (pin "1") (pinfunction "1_1") (pintype "passive"))
      (node (ref "TR1") (pin "4") (pinfunction "S1_4") (pintype "passive"))
    )
    (net (code "72") (name "Net-(C21-Pad1)") (class "Default")
      (node (ref "C21") (pin "1") (pinfunction "1_1") (pintype "passive"))
      (node (ref "C22") (pin "2") (pinfunction "2_2") (pintype "passive"))
      (node (ref "J2") (pin "2") (pinfunction "2_2") (pintype "bidirectional"))
      (node (ref "R10") (pin "1") (pinfunction "1_1") (pintype "passive"))
      (node (ref "TR1") (pin "1") (pinfunction "P1_1") (pintype "passive"))
      (node (ref "TR1") (pin "2") (pinfunction "P1_2") (pintype "passive"))
    )
    (net (code "73") (name "Net-(C32-Pad2)") (class "Default")
      (node (ref "C32") (pin "2") (pinfunction "2_2") (pintype "passive"))
      (node (ref "C33") (pin "2") (pinfunction "2_2") (pintype "passive"))
      (node (ref "R18") (pin "1") (pinfunction "1_1") (pintype "passive"))
    )
    (net (code "74") (name "Net-(C44-Pad2)") (class "Default")
      (node (ref "C44") (pin "2") (pinfunction "2_2") (pintype "passive"))
      (node (ref "R22") (pin "1") (pinfunction "1_1") (pintype "passive"))
    )
    (net (code "75") (name "Net-(IC6-IN_SEL)") (class "Default")
      (node (ref "IC6") (pin "32") (pinfunction "IN_SEL_32") (pintype "input"))
      (node (ref "R7") (pin "2") (pinfunction "2_2") (pintype "passive"))
    )
    (net (code "76") (name "Net-(IC6-VREF0)") (class "Default")
      (node (ref "IC6") (pin "3") (pinfunction "VREF0_3") (pintype "input"))
      (node (ref "R13") (pin "2") (pinfunction "2_2") (pintype "passive"))
    )
    (net (code "77") (name "Net-(IC6-VREF1)") (class "Default")
      (node (ref "IC6") (pin "8") (pinfunction "VREF1_8") (pintype "input"))
      (node (ref "R17") (pin "2") (pinfunction "2_2") (pintype "passive"))
    )
    (net (code "78") (name "Net-(IC6-VT0)") (class "Default")
      (node (ref "C23") (pin "2") (pinfunction "2_2") (pintype "passive"))
      (node (ref "IC6") (pin "4") (pinfunction "VT0_4") (pintype "passive"))
      (node (ref "R13") (pin "1") (pinfunction "1_1") (pintype "passive"))
    )
    (net (code "79") (name "Net-(IC6-VT1)") (class "Default")
      (node (ref "C26") (pin "2") (pinfunction "2_2") (pintype "passive"))
      (node (ref "IC6") (pin "7") (pinfunction "VT1_7") (pintype "passive"))
      (node (ref "R17") (pin "1") (pinfunction "1_1") (pintype "passive"))
    )
    (net (code "80") (name "Net-(IC7-VREF0)") (class "Default")
      (node (ref "IC7") (pin "3") (pinfunction "VREF0_3") (pintype "input"))
      (node (ref "R21") (pin "2") (pinfunction "2_2") (pintype "passive"))
    )
    (net (code "81") (name "Net-(IC7-VREF1)") (class "Default")
      (node (ref "IC7") (pin "8") (pinfunction "VREF1_8") (pintype "input"))
      (node (ref "R23") (pin "2") (pinfunction "2_2") (pintype "passive"))
    )
    (net (code "82") (name "Net-(IC7-VT0)") (class "Default")
      (node (ref "C42") (pin "2") (pinfunction "2_2") (pintype "passive"))
      (node (ref "IC7") (pin "4") (pinfunction "VT0_4") (pintype "passive"))
      (node (ref "R21") (pin "1") (pinfunction "1_1") (pintype "passive"))
    )
    (net (code "83") (name "Net-(IC7-VT1)") (class "Default")
      (node (ref "C47") (pin "2") (pinfunction "2_2") (pintype "passive"))
      (node (ref "IC7") (pin "7") (pinfunction "VT1_7") (pintype "passive"))
      (node (ref "R23") (pin "1") (pinfunction "1_1") (pintype "passive"))
    )
    (net (code "84") (name "Net-(IC7-~{Q0})") (class "Default")
      (node (ref "IC7") (pin "29") (pinfunction "~{Q0}_29") (pintype "output"))
      (node (ref "R20") (pin "1") (pinfunction "1_1") (pintype "passive"))
    )
    (net (code "85") (name "Net-(IC8-BIAS)") (class "Default")
      (node (ref "C48") (pin "1") (pinfunction "1_1") (pintype "passive"))
      (node (ref "IC8") (pin "40") (pinfunction "BIAS_40") (pintype "passive"))
    )
    (net (code "86") (name "Net-(IC8-CP)") (class "Default")
      (node (ref "C31") (pin "2") (pinfunction "2_2") (pintype "passive"))
      (node (ref "C34") (pin "2") (pinfunction "2_2") (pintype "passive"))
      (node (ref "IC8") (pin "4") (pinfunction "CP_4") (pintype "output"))
      (node (ref "R16") (pin "2") (pinfunction "2_2") (pintype "passive"))
      (node (ref "R18") (pin "2") (pinfunction "2_2") (pintype "passive"))
    )
    (net (code "87") (name "Net-(IC8-DVDD3V)") (class "Default")
      (node (ref "C61") (pin "2") (pinfunction "2_2") (pintype "passive"))
      (node (ref "C62") (pin "2") (pinfunction "2_2") (pintype "passive"))
      (node (ref "IC8") (pin "16") (pinfunction "DVDD3V_16") (pintype "power_in"))
      (node (ref "R24") (pin "1") (pinfunction "1_1") (pintype "passive"))
    )
    (net (code "88") (name "Net-(IC8-VCC1)") (class "Default")
      (node (ref "C45") (pin "2") (pinfunction "2_2") (pintype "passive"))
      (node (ref "C46") (pin "2") (pinfunction "2_2") (pintype "passive"))
      (node (ref "IC8") (pin "25") (pinfunction "VCC2_25") (pintype "power_in"))
      (node (ref "IC8") (pin "27") (pinfunction "VCC1_27") (pintype "power_in"))
      (node (ref "L7") (pin "1") (pinfunction "1_1") (pintype "passive"))
    )
    (net (code "89") (name "Net-(IC8-VTUNE)") (class "Default")
      (node (ref "C28") (pin "2") (pinfunction "2_2") (pintype "passive"))
      (node (ref "C29") (pin "2") (pinfunction "2_2") (pintype "passive"))
      (node (ref "IC8") (pin "23") (pinfunction "VTUNE_23") (pintype "input"))
      (node (ref "R16") (pin "1") (pinfunction "1_1") (pintype "passive"))
    )
    (net (code "90") (name "Net-(IC8-XREFP)") (class "Default")
      (node (ref "C43") (pin "2") (pinfunction "2_2") (pintype "passive"))
      (node (ref "IC8") (pin "15") (pinfunction "XREFP_15") (pintype "input"))
      (node (ref "R22") (pin "2") (pinfunction "2_2") (pintype "passive"))
    )
    (net (code "91") (name "Net-(IC9-CLK0)") (class "Default")
      (node (ref "C68") (pin "2") (pinfunction "2_2") (pintype "passive"))
      (node (ref "IC9") (pin "14") (pinfunction "CLK0_14") (pintype "input"))
      (node (ref "R31") (pin "2") (pinfunction "2_2") (pintype "passive"))
    )
    (net (code "92") (name "Net-(IC9-OEA)") (class "Default")
      (node (ref "IC9") (pin "16") (pinfunction "OEA_16") (pintype "input"))
      (node (ref "R27") (pin "2") (pinfunction "2_2") (pintype "passive"))
      (node (ref "R29") (pin "1") (pinfunction "1_1") (pintype "passive"))
    )
    (net (code "93") (name "Net-(IC9-OEB)") (class "Default")
      (node (ref "IC9") (pin "18") (pinfunction "OEB_18") (pintype "input"))
      (node (ref "R33") (pin "2") (pinfunction "2_2") (pintype "passive"))
      (node (ref "R35") (pin "1") (pinfunction "1_1") (pintype "passive"))
    )
    (net (code "94") (name "Net-(IC9-VREF)") (class "Default")
      (node (ref "C72") (pin "2") (pinfunction "2_2") (pintype "passive"))
      (node (ref "IC9") (pin "17") (pinfunction "VREF_17") (pintype "input"))
    )
    (net (code "95") (name "Net-(IC9-~{CLK0})") (class "Default")
      (node (ref "C70") (pin "2") (pinfunction "2_2") (pintype "passive"))
      (node (ref "IC9") (pin "15") (pinfunction "~{CLK0}_15") (pintype "input"))
      (node (ref "R31") (pin "1") (pinfunction "1_1") (pintype "passive"))
    )
    (net (code "96") (name "Net-(IC10-CLK0)") (class "Default")
      (node (ref "C69") (pin "2") (pinfunction "2_2") (pintype "passive"))
      (node (ref "IC10") (pin "14") (pinfunction "CLK0_14") (pintype "input"))
      (node (ref "R32") (pin "2") (pinfunction "2_2") (pintype "passive"))
    )
    (net (code "97") (name "Net-(IC10-OEA)") (class "Default")
      (node (ref "IC10") (pin "16") (pinfunction "OEA_16") (pintype "input"))
      (node (ref "R28") (pin "2") (pinfunction "2_2") (pintype "passive"))
      (node (ref "R30") (pin "1") (pinfunction "1_1") (pintype "passive"))
    )
    (net (code "98") (name "Net-(IC10-OEB)") (class "Default")
      (node (ref "IC10") (pin "18") (pinfunction "OEB_18") (pintype "input"))
      (node (ref "R34") (pin "2") (pinfunction "2_2") (pintype "passive"))
      (node (ref "R36") (pin "1") (pinfunction "1_1") (pintype "passive"))
    )
    (net (code "99") (name "Net-(IC10-VREF)") (class "Default")
      (node (ref "C73") (pin "2") (pinfunction "2_2") (pintype "passive"))
      (node (ref "IC10") (pin "17") (pinfunction "VREF_17") (pintype "input"))
    )
    (net (code "100") (name "Net-(IC10-~{CLK0})") (class "Default")
      (node (ref "C71") (pin "2") (pinfunction "2_2") (pintype "passive"))
      (node (ref "IC10") (pin "15") (pinfunction "~{CLK0}_15") (pintype "input"))
      (node (ref "R32") (pin "1") (pinfunction "1_1") (pintype "passive"))
    )
    (net (code "101") (name "P2V5_CLK1") (class "Default")
      (node (ref "L10") (pin "2") (pinfunction "2_2") (pintype "passive"))
    )
    (net (code "102") (name "P2V5_CLK2") (class "Default")
      (node (ref "L11") (pin "2") (pinfunction "2_2") (pintype "passive"))
    )
    (net (code "103") (name "P3V3_CLK") (class "Default")
      (node (ref "C48") (pin "2") (pinfunction "2_2") (pintype "passive"))
      (node (ref "C59") (pin "2") (pinfunction "2_2") (pintype "passive"))
      (node (ref "C60") (pin "2") (pinfunction "2_2") (pintype "passive"))
      (node (ref "C63") (pin "2") (pinfunction "2_2") (pintype "passive"))
      (node (ref "C64") (pin "2") (pinfunction "2_2") (pintype "passive"))
      (node (ref "C65") (pin "2") (pinfunction "2_2") (pintype "passive"))
      (node (ref "C66") (pin "2") (pinfunction "2_2") (pintype "passive"))
      (node (ref "C67") (pin "2") (pinfunction "2_2") (pintype "passive"))
      (node (ref "IC8") (pin "1") (pinfunction "AVDD_1") (pintype "power_in"))
      (node (ref "IC8") (pin "10") (pinfunction "RVDD_10") (pintype "power_in"))
      (node (ref "IC8") (pin "17") (pinfunction "CEN_17") (pintype "input"))
      (node (ref "IC8") (pin "35") (pinfunction "VCCHF_35") (pintype "power_in"))
      (node (ref "IC8") (pin "36") (pinfunction "VCCPS_36") (pintype "power_in"))
      (node (ref "IC8") (pin "39") (pinfunction "VCCPD_39") (pintype "power_in"))
      (node (ref "R24") (pin "2") (pinfunction "2_2") (pintype "passive"))
    )
    (net (code "104") (name "P3V3_CLKDIS1") (class "Default")
      (node (ref "L6") (pin "2") (pinfunction "2_2") (pintype "passive"))
      (node (ref "L9") (pin "2") (pinfunction "2_2") (pintype "passive"))
    )
    (net (code "105") (name "P3V3_CLKDIS1F") (class "Default")
      (node (ref "C52") (pin "2") (pinfunction "2_2") (pintype "passive"))
      (node (ref "C53") (pin "2") (pinfunction "2_2") (pintype "passive"))
      (node (ref "C54") (pin "2") (pinfunction "2_2") (pintype "passive"))
      (node (ref "C55") (pin "2") (pinfunction "2_2") (pintype "passive"))
      (node (ref "C56") (pin "2") (pinfunction "2_2") (pintype "passive"))
      (node (ref "C57") (pin "2") (pinfunction "2_2") (pintype "passive"))
      (node (ref "C58") (pin "2") (pinfunction "2_2") (pintype "passive"))
      (node (ref "IC7") (pin "10") (pinfunction "VCC_10") (pintype "power_in"))
      (node (ref "IC7") (pin "15") (pinfunction "VCC_15") (pintype "power_in"))
      (node (ref "IC7") (pin "16") (pinfunction "VCC_16") (pintype "power_in"))
      (node (ref "IC7") (pin "25") (pinfunction "VCC_25") (pintype "power_in"))
      (node (ref "IC7") (pin "26") (pinfunction "VCC_26") (pintype "power_in"))
      (node (ref "IC7") (pin "31") (pinfunction "VCC_31") (pintype "power_in"))
      (node (ref "L9") (pin "1") (pinfunction "1_1") (pintype "passive"))
    )
    (net (code "106") (name "P5V0_CLK") (class "Default")
      (node (ref "L7") (pin "2") (pinfunction "2_2") (pintype "passive"))
      (node (ref "L8") (pin "2") (pinfunction "2_2") (pintype "passive"))
    )
    (net (code "107") (name "unconnected-(C24-Pad2)") (class "Default")
      (node (ref "C24") (pin "2") (pinfunction "2_2") (pintype "passive"))
    )
    (net (code "108") (name "unconnected-(C25-Pad2)") (class "Default")
      (node (ref "C25") (pin "2") (pinfunction "2_2") (pintype "passive"))
    )
    (net (code "109") (name "unconnected-(IC6-CLK1-Pad5)") (class "Default")
      (node (ref "IC6") (pin "5") (pinfunction "CLK1_5") (pintype "input+no_connect"))
    )
    (net (code "110") (name "unconnected-(IC6-NC-Pad9)") (class "Default")
      (node (ref "IC6") (pin "9") (pinfunction "NC_9") (pintype "passive+no_connect"))
    )
    (net (code "111") (name "unconnected-(IC6-Q3-Pad22)") (class "Default")
      (node (ref "IC6") (pin "22") (pinfunction "Q3_22") (pintype "output+no_connect"))
    )
    (net (code "112") (name "unconnected-(IC6-Q4-Pad20)") (class "Default")
      (node (ref "IC6") (pin "20") (pinfunction "Q4_20") (pintype "output+no_connect"))
    )
    (net (code "113") (name "unconnected-(IC6-Q5-Pad18)") (class "Default")
      (node (ref "IC6") (pin "18") (pinfunction "Q5_18") (pintype "output+no_connect"))
    )
    (net (code "114") (name "unconnected-(IC6-Q6-Pad14)") (class "Default")
      (node (ref "IC6") (pin "14") (pinfunction "Q6_14") (pintype "output+no_connect"))
    )
    (net (code "115") (name "unconnected-(IC6-Q7-Pad12)") (class "Default")
      (node (ref "IC6") (pin "12") (pinfunction "Q7_12") (pintype "output+no_connect"))
    )
    (net (code "116") (name "unconnected-(IC6-~{CLK1}-Pad6)") (class "Default")
      (node (ref "IC6") (pin "6") (pinfunction "~{CLK1}_6") (pintype "input+no_connect"))
    )
    (net (code "117") (name "unconnected-(IC6-~{Q3}-Pad21)") (class "Default")
      (node (ref "IC6") (pin "21") (pinfunction "~{Q3}_21") (pintype "output+no_connect"))
    )
    (net (code "118") (name "unconnected-(IC6-~{Q4}-Pad19)") (class "Default")
      (node (ref "IC6") (pin "19") (pinfunction "~{Q4}_19") (pintype "output+no_connect"))
    )
    (net (code "119") (name "unconnected-(IC6-~{Q5}-Pad17)") (class "Default")
      (node (ref "IC6") (pin "17") (pinfunction "~{Q5}_17") (pintype "output+no_connect"))
    )
    (net (code "120") (name "unconnected-(IC6-~{Q6}-Pad13)") (class "Default")
      (node (ref "IC6") (pin "13") (pinfunction "~{Q6}_13") (pintype "output+no_connect"))
    )
    (net (code "121") (name "unconnected-(IC6-~{Q7}-Pad11)") (class "Default")
      (node (ref "IC6") (pin "11") (pinfunction "~{Q7}_11") (pintype "output+no_connect"))
    )
    (net (code "122") (name "unconnected-(IC7-NC-Pad9)") (class "Default")
      (node (ref "IC7") (pin "9") (pinfunction "NC_9") (pintype "passive+no_connect"))
    )
    (net (code "123") (name "unconnected-(IC7-Q1-Pad28)") (class "Default")
      (node (ref "IC7") (pin "28") (pinfunction "Q1_28") (pintype "output+no_connect"))
    )
    (net (code "124") (name "unconnected-(IC7-Q2-Pad24)") (class "Default")
      (node (ref "IC7") (pin "24") (pinfunction "Q2_24") (pintype "output+no_connect"))
    )
    (net (code "125") (name "unconnected-(IC7-Q3-Pad22)") (class "Default")
      (node (ref "IC7") (pin "22") (pinfunction "Q3_22") (pintype "output+no_connect"))
    )
    (net (code "126") (name "unconnected-(IC7-Q4-Pad20)") (class "Default")
      (node (ref "IC7") (pin "20") (pinfunction "Q4_20") (pintype "output+no_connect"))
    )
    (net (code "127") (name "unconnected-(IC7-Q5-Pad18)") (class "Default")
      (node (ref "IC7") (pin "18") (pinfunction "Q5_18") (pintype "output+no_connect"))
    )
    (net (code "128") (name "unconnected-(IC7-Q6-Pad14)") (class "Default")
      (node (ref "IC7") (pin "14") (pinfunction "Q6_14") (pintype "output+no_connect"))
    )
    (net (code "129") (name "unconnected-(IC7-Q7-Pad12)") (class "Default")
      (node (ref "IC7") (pin "12") (pinfunction "Q7_12") (pintype "output+no_connect"))
    )
    (net (code "130") (name "unconnected-(IC7-~{Q1}-Pad27)") (class "Default")
      (node (ref "IC7") (pin "27") (pinfunction "~{Q1}_27") (pintype "output+no_connect"))
    )
    (net (code "131") (name "unconnected-(IC7-~{Q2}-Pad23)") (class "Default")
      (node (ref "IC7") (pin "23") (pinfunction "~{Q2}_23") (pintype "output+no_connect"))
    )
    (net (code "132") (name "unconnected-(IC7-~{Q3}-Pad21)") (class "Default")
      (node (ref "IC7") (pin "21") (pinfunction "~{Q3}_21") (pintype "output+no_connect"))
    )
    (net (code "133") (name "unconnected-(IC7-~{Q4}-Pad19)") (class "Default")
      (node (ref "IC7") (pin "19") (pinfunction "~{Q4}_19") (pintype "output+no_connect"))
    )
    (net (code "134") (name "unconnected-(IC7-~{Q5}-Pad17)") (class "Default")
      (node (ref "IC7") (pin "17") (pinfunction "~{Q5}_17") (pintype "output+no_connect"))
    )
    (net (code "135") (name "unconnected-(IC7-~{Q6}-Pad13)") (class "Default")
      (node (ref "IC7") (pin "13") (pinfunction "~{Q6}_13") (pintype "output+no_connect"))
    )
    (net (code "136") (name "unconnected-(IC7-~{Q7}-Pad11)") (class "Default")
      (node (ref "IC7") (pin "11") (pinfunction "~{Q7}_11") (pintype "output+no_connect"))
    )
    (net (code "137") (name "unconnected-(IC8-NC-Pad2)") (class "Default")
      (node (ref "IC8") (pin "2") (pinfunction "NC_2") (pintype "passive+no_connect"))
    )
    (net (code "138") (name "unconnected-(IC8-NC-Pad5)") (class "Default")
      (node (ref "IC8") (pin "5") (pinfunction "NC_5") (pintype "passive+no_connect"))
    )
    (net (code "139") (name "unconnected-(IC8-NC-Pad6)") (class "Default")
      (node (ref "IC8") (pin "6") (pinfunction "NC_6") (pintype "passive+no_connect"))
    )
    (net (code "140") (name "unconnected-(IC8-NC-Pad8)") (class "Default")
      (node (ref "IC8") (pin "8") (pinfunction "NC_8") (pintype "passive+no_connect"))
    )
    (net (code "141") (name "unconnected-(IC8-NC-Pad9)") (class "Default")
      (node (ref "IC8") (pin "9") (pinfunction "NC_9") (pintype "passive+no_connect"))
    )
    (net (code "142") (name "unconnected-(IC8-NC-Pad11)") (class "Default")
      (node (ref "IC8") (pin "11") (pinfunction "NC_11") (pintype "passive+no_connect"))
    )
    (net (code "143") (name "unconnected-(IC8-NC-Pad12)") (class "Default")
      (node (ref "IC8") (pin "12") (pinfunction "NC_12") (pintype "passive+no_connect"))
    )
    (net (code "144") (name "unconnected-(IC8-NC-Pad13)") (class "Default")
      (node (ref "IC8") (pin "13") (pinfunction "NC_13") (pintype "passive+no_connect"))
    )
    (net (code "145") (name "unconnected-(IC8-NC-Pad14)") (class "Default")
      (node (ref "IC8") (pin "14") (pinfunction "NC_14") (pintype "passive+no_connect"))
    )
    (net (code "146") (name "unconnected-(IC8-NC-Pad18)") (class "Default")
      (node (ref "IC8") (pin "18") (pinfunction "NC_18") (pintype "passive+no_connect"))
    )
    (net (code "147") (name "unconnected-(IC8-NC-Pad19)") (class "Default")
      (node (ref "IC8") (pin "19") (pinfunction "NC_19") (pintype "passive+no_connect"))
    )
    (net (code "148") (name "unconnected-(IC8-NC-Pad20)") (class "Default")
      (node (ref "IC8") (pin "20") (pinfunction "NC_20") (pintype "passive+no_connect"))
    )
    (net (code "149") (name "unconnected-(IC8-NC-Pad21)") (class "Default")
      (node (ref "IC8") (pin "21") (pinfunction "NC_21") (pintype "passive+no_connect"))
    )
    (net (code "150") (name "unconnected-(IC8-NC-Pad22)") (class "Default")
      (node (ref "IC8") (pin "22") (pinfunction "NC_22") (pintype "passive+no_connect"))
    )
    (net (code "151") (name "unconnected-(IC8-NC-Pad24)") (class "Default")
      (node (ref "IC8") (pin "24") (pinfunction "NC_24") (pintype "passive+no_connect"))
    )
    (net (code "152") (name "unconnected-(IC8-NC-Pad26)") (class "Default")
      (node (ref "IC8") (pin "26") (pinfunction "NC_26") (pintype "passive+no_connect"))
    )
    (net (code "153") (name "unconnected-(IC8-NC-Pad34)") (class "Default")
      (node (ref "IC8") (pin "34") (pinfunction "NC_34") (pintype "passive+no_connect"))
    )
    (net (code "154") (name "unconnected-(IC8-NC-Pad37)") (class "Default")
      (node (ref "IC8") (pin "37") (pinfunction "NC_37") (pintype "passive+no_connect"))
    )
    (net (code "155") (name "unconnected-(IC8-NC-Pad38)") (class "Default")
      (node (ref "IC8") (pin "38") (pinfunction "NC_38") (pintype "passive+no_connect"))
    )
    (net (code "156") (name "unconnected-(IC9-CLK1-Pad19)") (class "Default")
      (node (ref "IC9") (pin "19") (pinfunction "CLK1_19") (pintype "input+no_connect"))
    )
    (net (code "157") (name "unconnected-(IC9-CLK_SEL-Pad23)") (class "Default")
      (node (ref "IC9") (pin "23") (pinfunction "CLK_SEL_23") (pintype "input+no_connect"))
    )
    (net (code "158") (name "unconnected-(IC9-DIVA-Pad1)") (class "Default")
      (node (ref "IC9") (pin "1") (pinfunction "DIVA_1") (pintype "input+no_connect"))
    )
    (net (code "159") (name "unconnected-(IC9-DIVB-Pad33)") (class "Default")
      (node (ref "IC9") (pin "33") (pinfunction "DIVB_33") (pintype "input+no_connect"))
    )
    (net (code "160") (name "unconnected-(IC9-NC-Pad11)") (class "Default")
      (node (ref "IC9") (pin "11") (pinfunction "NC_11") (pintype "passive+no_connect"))
    )
    (net (code "161") (name "unconnected-(IC9-NC-Pad13)") (class "Default")
      (node (ref "IC9") (pin "13") (pinfunction "NC_13") (pintype "passive+no_connect"))
    )
    (net (code "162") (name "unconnected-(IC9-NC-Pad21)") (class "Default")
      (node (ref "IC9") (pin "21") (pinfunction "NC_21") (pintype "passive+no_connect"))
    )
    (net (code "163") (name "unconnected-(IC9-NC-Pad28)") (class "Default")
      (node (ref "IC9") (pin "28") (pinfunction "NC_28") (pintype "passive+no_connect"))
    )
    (net (code "164") (name "unconnected-(IC9-~{CLK1}-Pad20)") (class "Default")
      (node (ref "IC9") (pin "20") (pinfunction "~{CLK1}_20") (pintype "input+no_connect"))
    )
    (net (code "165") (name "unconnected-(IC10-CLK1-Pad19)") (class "Default")
      (node (ref "IC10") (pin "19") (pinfunction "CLK1_19") (pintype "input+no_connect"))
    )
    (net (code "166") (name "unconnected-(IC10-CLK_SEL-Pad23)") (class "Default")
      (node (ref "IC10") (pin "23") (pinfunction "CLK_SEL_23") (pintype "input+no_connect"))
    )
    (net (code "167") (name "unconnected-(IC10-DIVA-Pad1)") (class "Default")
      (node (ref "IC10") (pin "1") (pinfunction "DIVA_1") (pintype "input+no_connect"))
    )
    (net (code "168") (name "unconnected-(IC10-DIVB-Pad33)") (class "Default")
      (node (ref "IC10") (pin "33") (pinfunction "DIVB_33") (pintype "input+no_connect"))
    )
    (net (code "169") (name "unconnected-(IC10-NC-Pad11)") (class "Default")
      (node (ref "IC10") (pin "11") (pinfunction "NC_11") (pintype "passive+no_connect"))
    )
    (net (code "170") (name "unconnected-(IC10-NC-Pad13)") (class "Default")
      (node (ref "IC10") (pin "13") (pinfunction "NC_13") (pintype "passive+no_connect"))
    )
    (net (code "171") (name "unconnected-(IC10-NC-Pad21)") (class "Default")
      (node (ref "IC10") (pin "21") (pinfunction "NC_21") (pintype "passive+no_connect"))
    )
    (net (code "172") (name "unconnected-(IC10-NC-Pad28)") (class "Default")
      (node (ref "IC10") (pin "28") (pinfunction "NC_28") (pintype "passive+no_connect"))
    )
    (net (code "173") (name "unconnected-(IC10-Q8-Pad27)") (class "Default")
      (node (ref "IC10") (pin "27") (pinfunction "Q8_27") (pintype "output+no_connect"))
    )
    (net (code "174") (name "unconnected-(IC10-Q9-Pad25)") (class "Default")
      (node (ref "IC10") (pin "25") (pinfunction "Q9_25") (pintype "output+no_connect"))
    )
    (net (code "175") (name "unconnected-(IC10-~{CLK1}-Pad20)") (class "Default")
      (node (ref "IC10") (pin "20") (pinfunction "~{CLK1}_20") (pintype "input+no_connect"))
    )
    (net (code "176") (name "unconnected-(IC10-~{Q8}-Pad26)") (class "Default")
      (node (ref "IC10") (pin "26") (pinfunction "~{Q8}_26") (pintype "output+no_connect"))
    )
    (net (code "177") (name "unconnected-(IC10-~{Q9}-Pad24)") (class "Default")
      (node (ref "IC10") (pin "24") (pinfunction "~{Q9}_24") (pintype "output+no_connect"))
    )
  )
)
